# pi3_hat.net
KiCad netlist of a schematic drawn in EAGLE
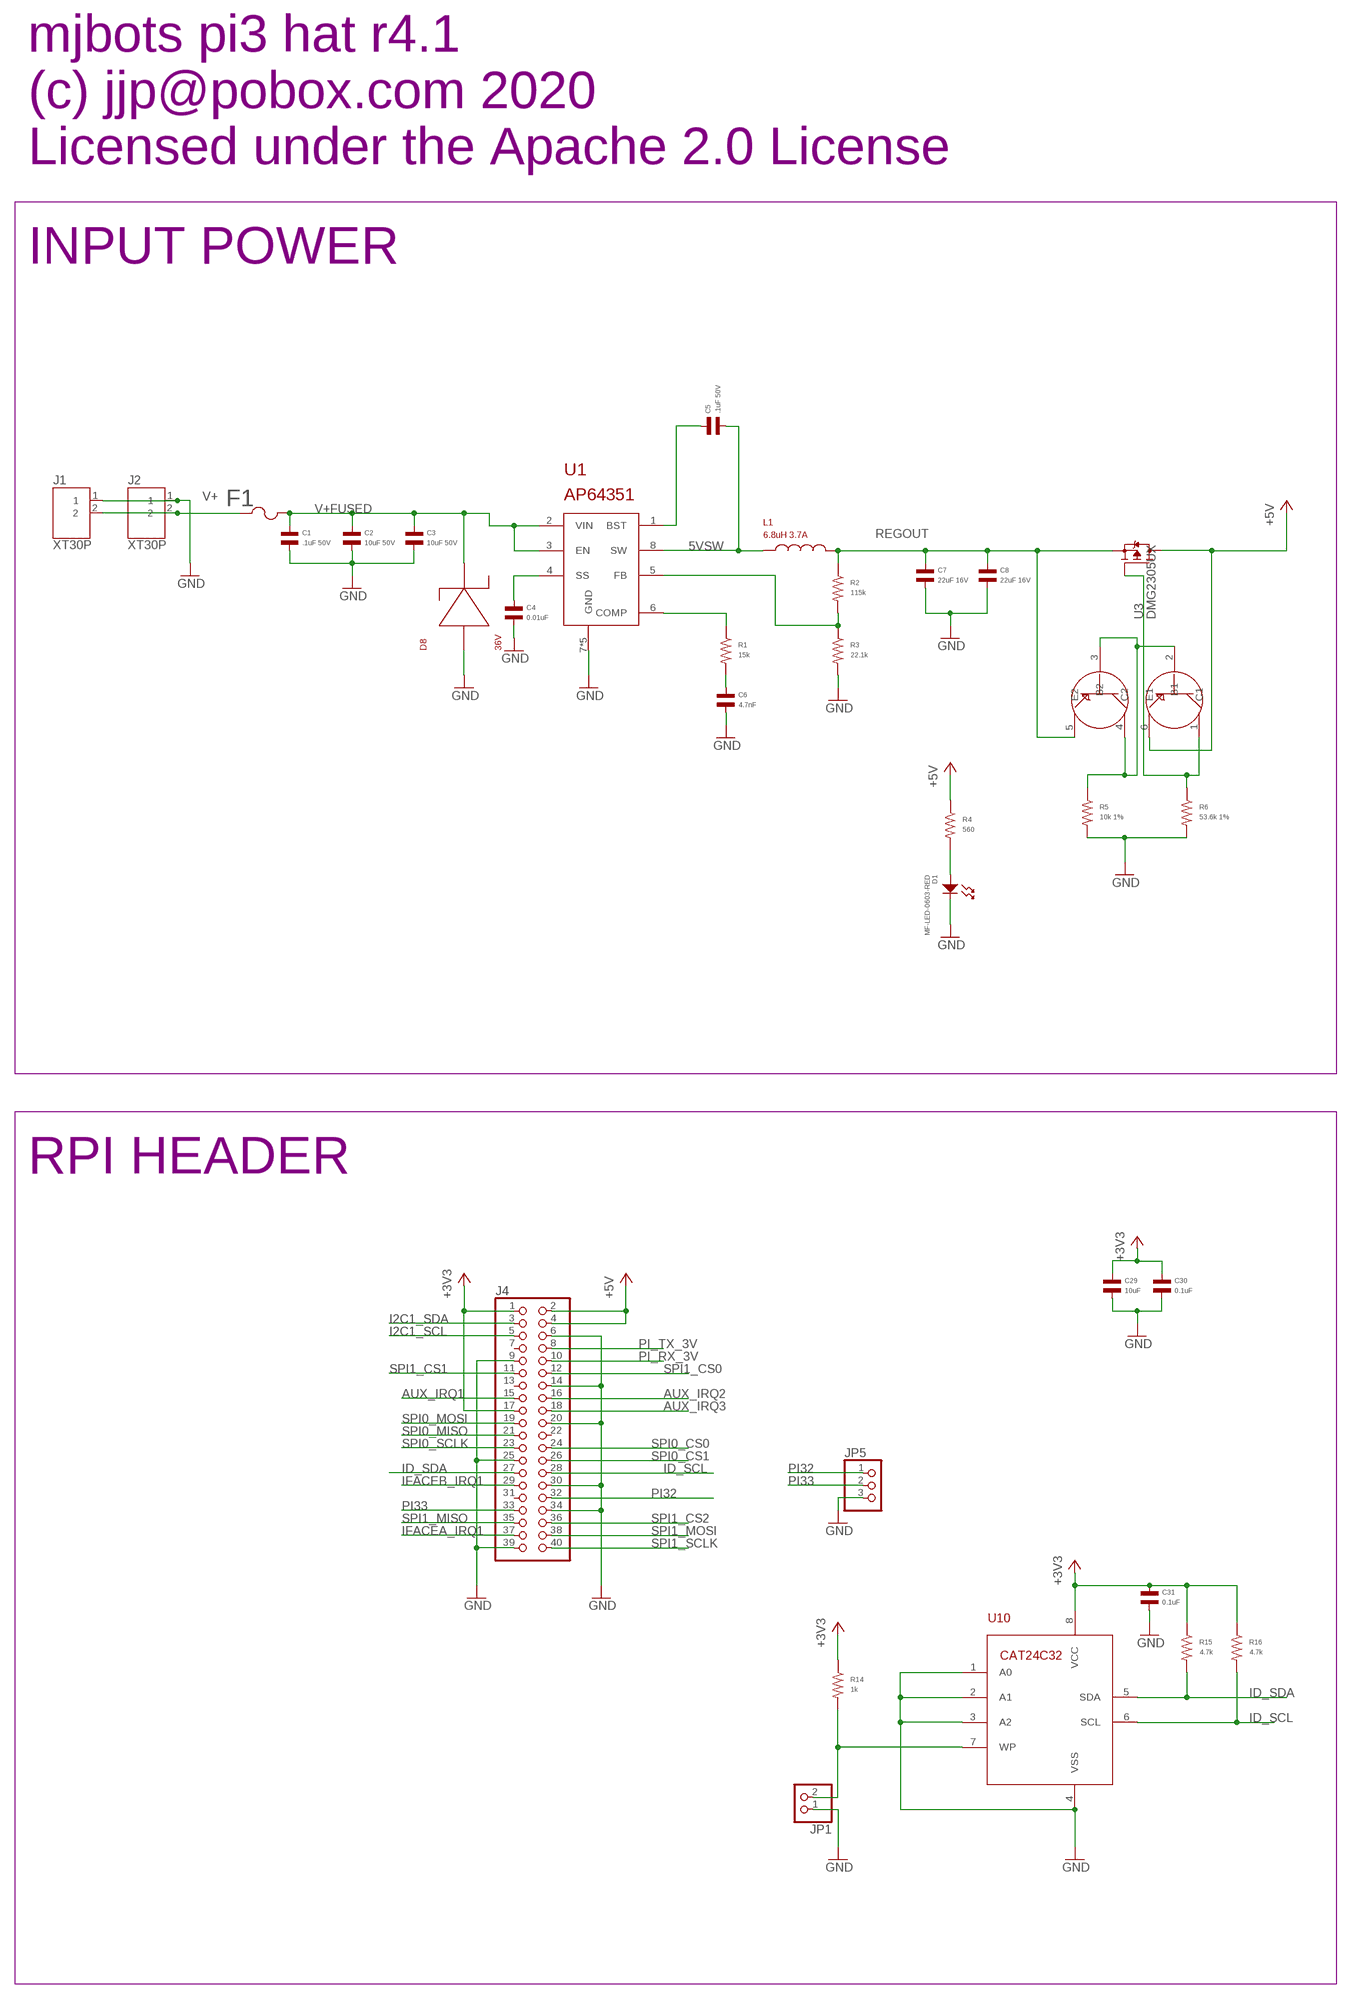
[diagram p0: schematic, sheet 1, part 1 of 3]
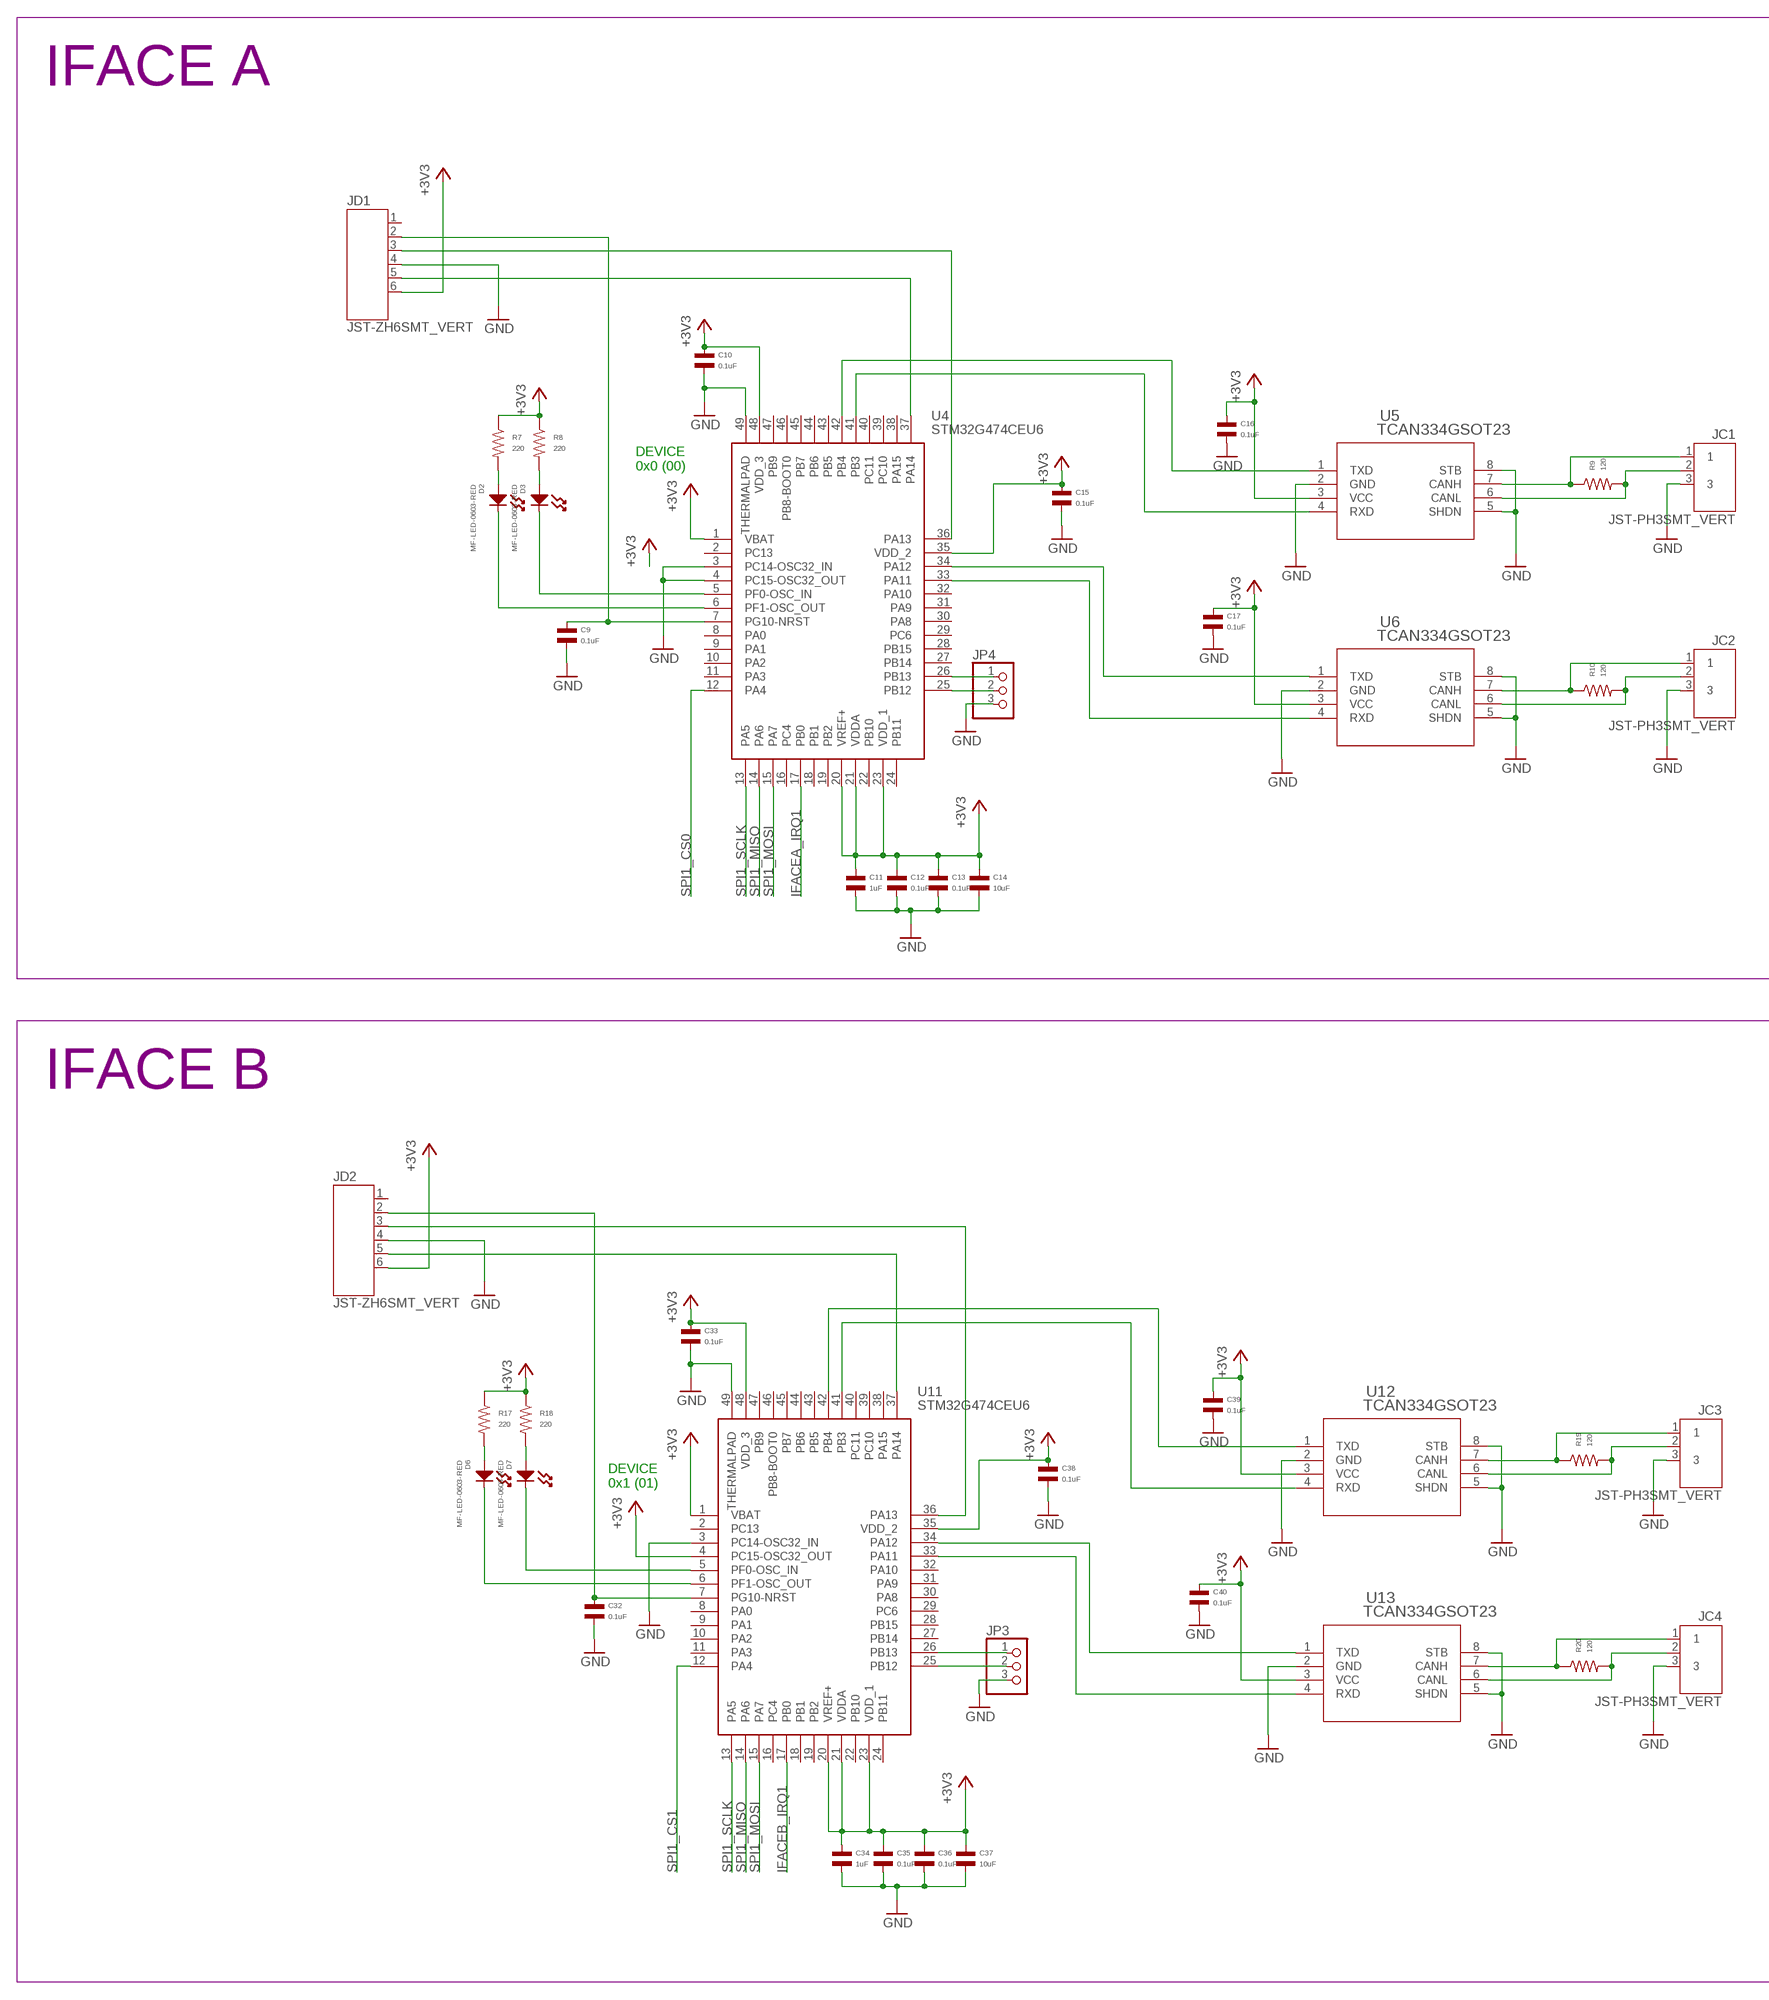
[diagram p1: schematic, sheet 1, part 2 of 3]
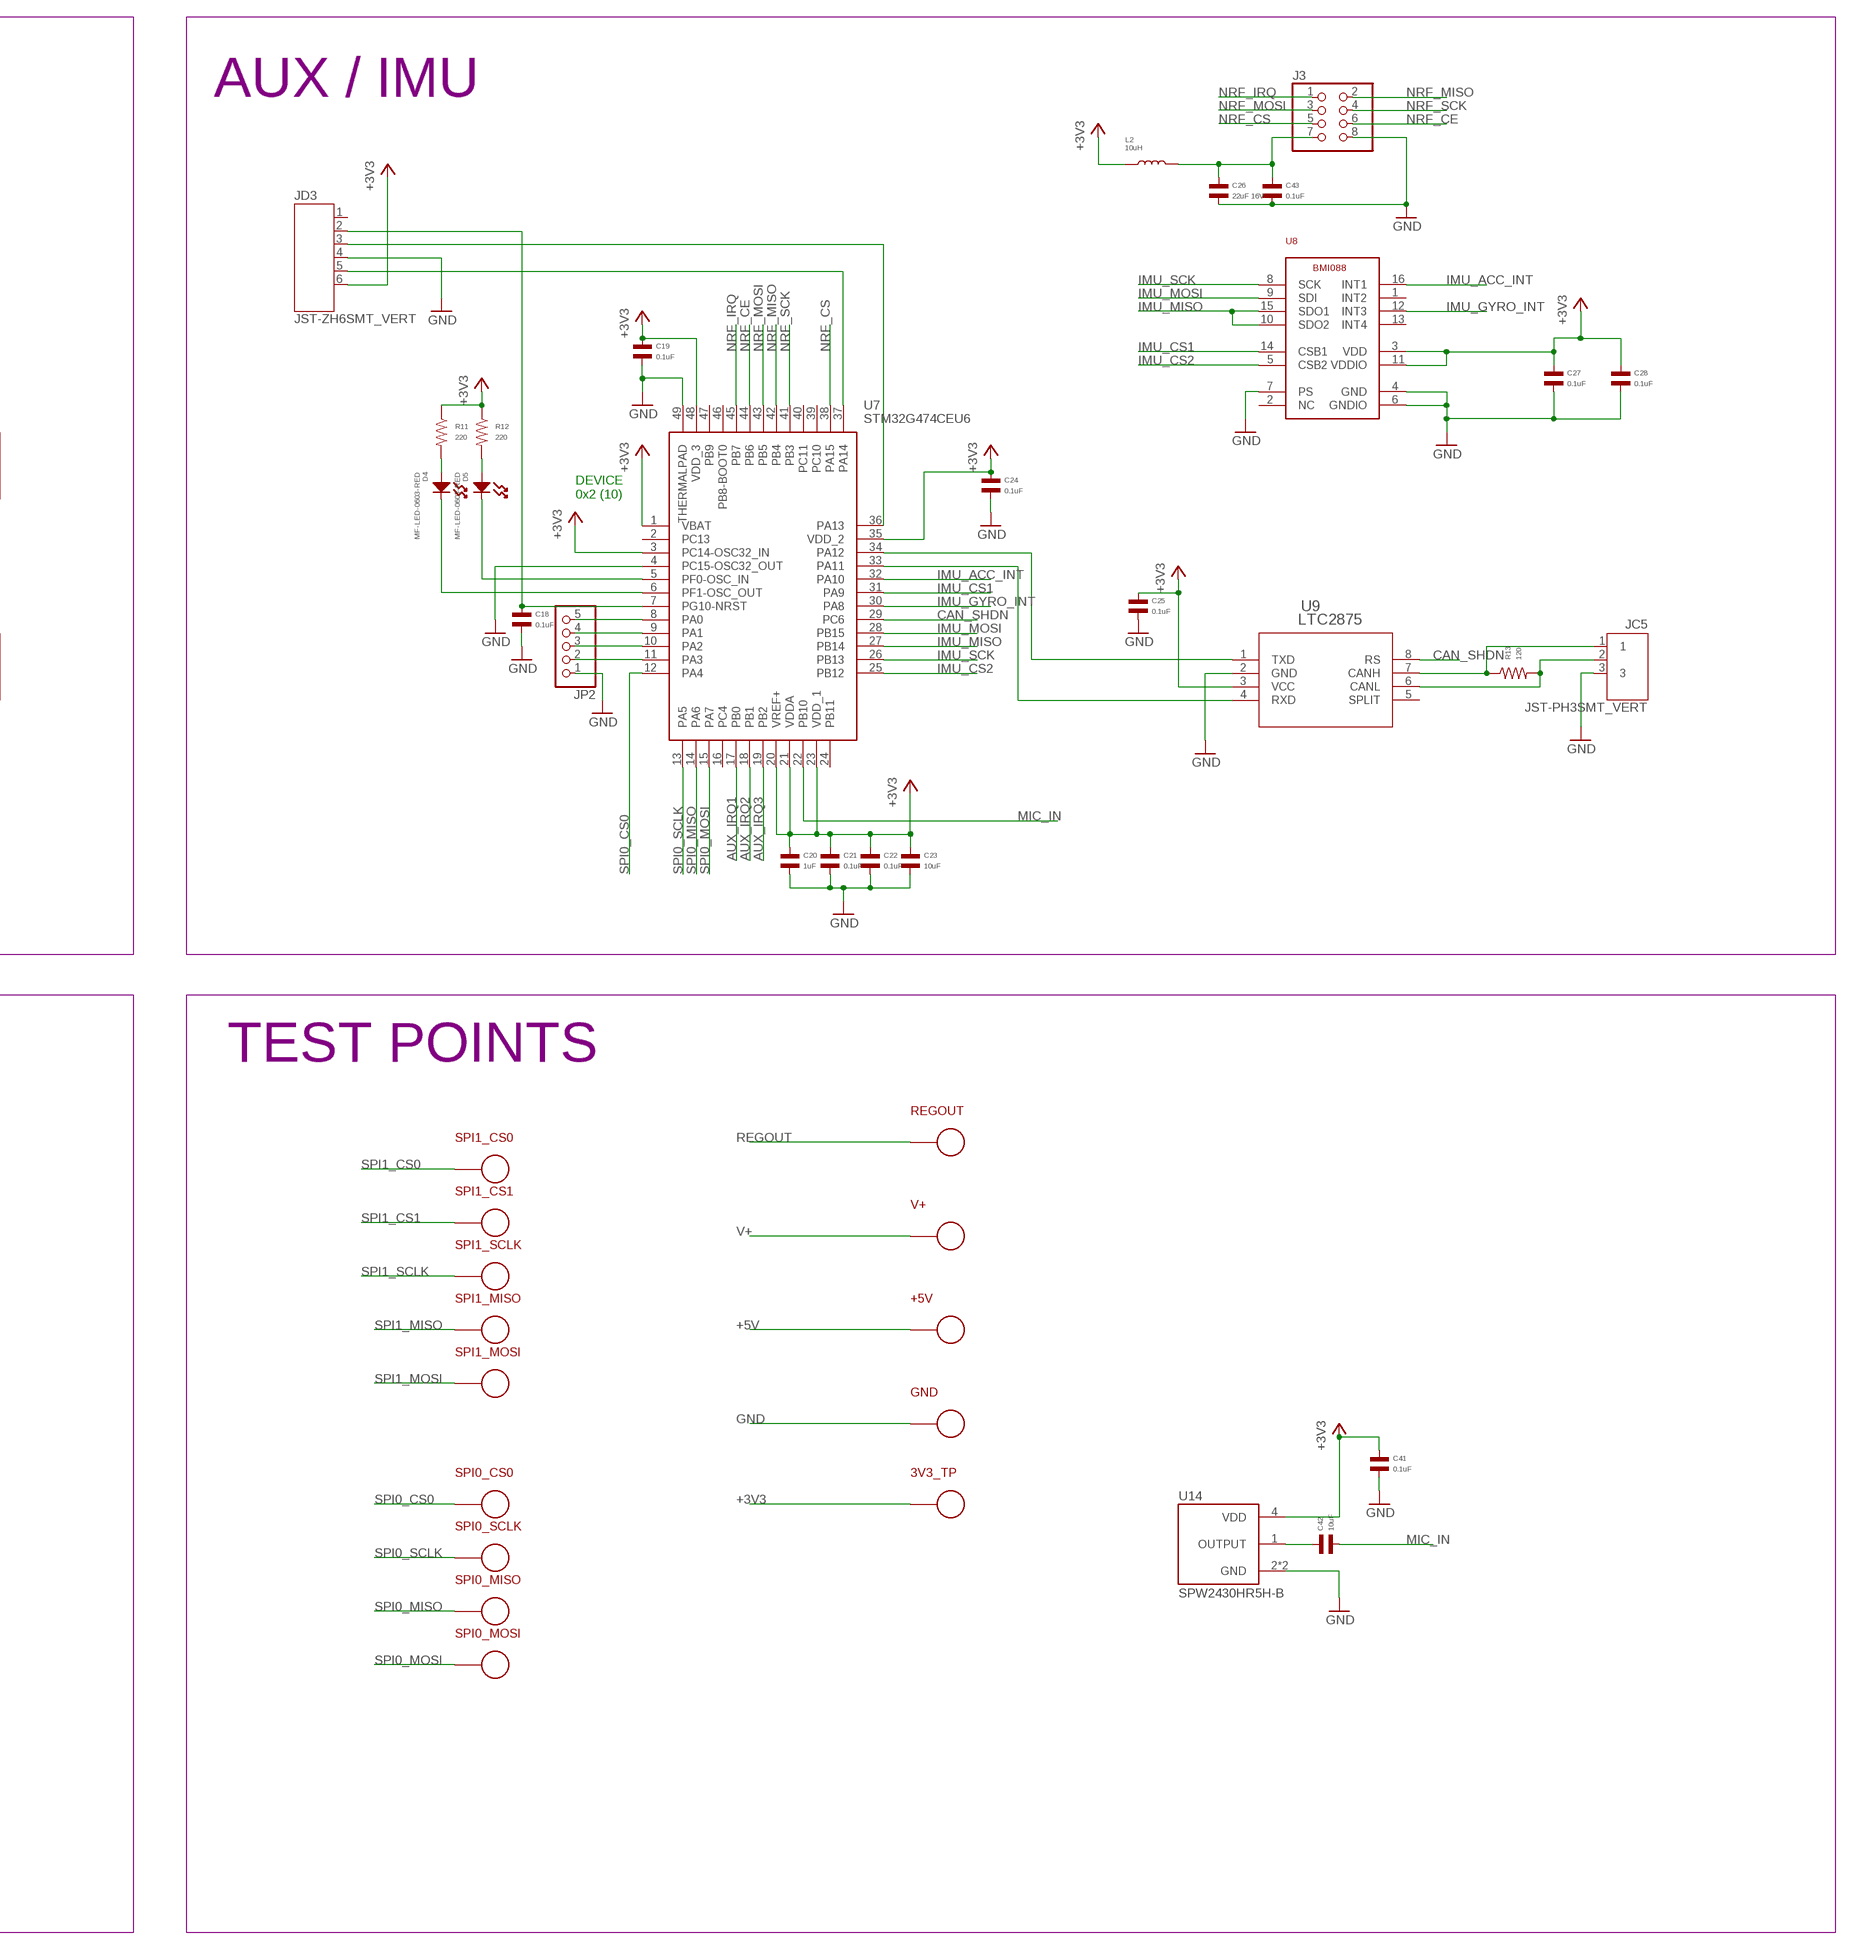
[diagram p2: schematic, sheet 1, part 3 of 3]

(export (version "E")
  (design (tool "Eeschema 10.0.6"))
  (components
    (comp (ref "+5V")
      (value "PAD24AWG_PAD")
      (footprint "eagle-import:24AWG_PAD")
      (libsource (lib "eagle-import") (part "PAD24AWG_PAD"))
    )
    (comp (ref "3V3_TP")
      (value "PAD24AWG_PAD")
      (footprint "eagle-import:24AWG_PAD")
      (libsource (lib "eagle-import") (part "PAD24AWG_PAD"))
    )
    (comp (ref "C1")
      (value ".1uF 50V")
      (footprint "eagle-import:C0805")
      (fields (field (name "HOUSEPART") "1") (field (name "MPN") "MF-CAP-0805-0.1uF"))
      (libsource (lib "eagle-import") (part "CAPACITOR_NP_0805"))
    )
    (comp (ref "C2")
      (value "10uF 50V")
      (footprint "eagle-import:C1206")
      (fields (field (name "MF") "TDK") (field (name "MPN") "CGA5L1X7R1H106K160AC"))
      (libsource (lib "eagle-import") (part "CAPACITOR_NP_1206"))
    )
    (comp (ref "C3")
      (value "10uF 50V")
      (footprint "eagle-import:C1206")
      (fields (field (name "MF") "TDK") (field (name "MPN") "CGA5L1X7R1H106K160AC"))
      (libsource (lib "eagle-import") (part "CAPACITOR_NP_1206"))
    )
    (comp (ref "C4")
      (value "0.01uF")
      (footprint "eagle-import:C0603")
      (fields (field (name "MPN") "MF-CAP-0603-0.01uF"))
      (libsource (lib "eagle-import") (part "CAPACITOR_NP_0603"))
    )
    (comp (ref "C5")
      (value ".1uF 50V")
      (footprint "eagle-import:C0805")
      (fields (field (name "HOUSEPART") "1") (field (name "MPN") "MF-CAP-0805-0.1uF"))
      (libsource (lib "eagle-import") (part "CAPACITOR_NP_0805"))
    )
    (comp (ref "C6")
      (value "4.7nF")
      (footprint "eagle-import:C0402")
      (fields (field (name "HOUSEPART") "YES") (field (name "MPN") "MF-CAP-0402-4.7nF"))
      (libsource (lib "eagle-import") (part "CAPACITOR_NP_0402"))
    )
    (comp (ref "C7")
      (value "22uF 16V")
      (footprint "eagle-import:C1210")
      (fields (field (name "MF") "SAMSUNG") (field (name "MPN") "CL32A226KOJNNNE"))
      (libsource (lib "eagle-import") (part "CAPACITOR_NP_1210"))
    )
    (comp (ref "C8")
      (value "22uF 16V")
      (footprint "eagle-import:C1210")
      (fields (field (name "MF") "SAMSUNG") (field (name "MPN") "CL32A226KOJNNNE"))
      (libsource (lib "eagle-import") (part "CAPACITOR_NP_1210"))
    )
    (comp (ref "C9")
      (value "0.1uF")
      (footprint "eagle-import:C0402")
      (fields (field (name "HOUSEPART") "YES") (field (name "MPN") "MF-CAP-0402-0.1uF"))
      (libsource (lib "eagle-import") (part "CAPACITOR_NP_0402"))
    )
    (comp (ref "C10")
      (value "0.1uF")
      (footprint "eagle-import:C0402")
      (fields (field (name "HOUSEPART") "YES") (field (name "MPN") "MF-CAP-0402-0.1uF"))
      (libsource (lib "eagle-import") (part "CAPACITOR_NP_0402"))
    )
    (comp (ref "C11")
      (value "1uF")
      (footprint "eagle-import:C0402")
      (fields (field (name "HOUSEPART") "YES") (field (name "MPN") "MF-CAP-0402-1uF"))
      (libsource (lib "eagle-import") (part "CAPACITOR_NP_0402"))
    )
    (comp (ref "C12")
      (value "0.1uF")
      (footprint "eagle-import:C0402")
      (fields (field (name "HOUSEPART") "YES") (field (name "MPN") "MF-CAP-0402-0.1uF"))
      (libsource (lib "eagle-import") (part "CAPACITOR_NP_0402"))
    )
    (comp (ref "C13")
      (value "0.1uF")
      (footprint "eagle-import:C0402")
      (fields (field (name "HOUSEPART") "YES") (field (name "MPN") "MF-CAP-0402-0.1uF"))
      (libsource (lib "eagle-import") (part "CAPACITOR_NP_0402"))
    )
    (comp (ref "C14")
      (value "10uF")
      (footprint "eagle-import:C1206")
      (fields (field (name "HOUSEPART") "YES") (field (name "MPN") "MF-CAP-1206-10uF"))
      (libsource (lib "eagle-import") (part "CAPACITOR_NP_1206"))
    )
    (comp (ref "C15")
      (value "0.1uF")
      (footprint "eagle-import:C0402")
      (fields (field (name "HOUSEPART") "YES") (field (name "MPN") "MF-CAP-0402-0.1uF"))
      (libsource (lib "eagle-import") (part "CAPACITOR_NP_0402"))
    )
    (comp (ref "C16")
      (value "0.1uF")
      (footprint "eagle-import:C0402")
      (fields (field (name "HOUSEPART") "YES") (field (name "MPN") "MF-CAP-0402-0.1uF"))
      (libsource (lib "eagle-import") (part "CAPACITOR_NP_0402"))
    )
    (comp (ref "C17")
      (value "0.1uF")
      (footprint "eagle-import:C0402")
      (fields (field (name "HOUSEPART") "YES") (field (name "MPN") "MF-CAP-0402-0.1uF"))
      (libsource (lib "eagle-import") (part "CAPACITOR_NP_0402"))
    )
    (comp (ref "C18")
      (value "0.1uF")
      (footprint "eagle-import:C0402")
      (fields (field (name "HOUSEPART") "YES") (field (name "MPN") "MF-CAP-0402-0.1uF"))
      (libsource (lib "eagle-import") (part "CAPACITOR_NP_0402"))
    )
    (comp (ref "C19")
      (value "0.1uF")
      (footprint "eagle-import:C0402")
      (fields (field (name "HOUSEPART") "YES") (field (name "MPN") "MF-CAP-0402-0.1uF"))
      (libsource (lib "eagle-import") (part "CAPACITOR_NP_0402"))
    )
    (comp (ref "C20")
      (value "1uF")
      (footprint "eagle-import:C0402")
      (fields (field (name "HOUSEPART") "YES") (field (name "MPN") "MF-CAP-0402-1uF"))
      (libsource (lib "eagle-import") (part "CAPACITOR_NP_0402"))
    )
    (comp (ref "C21")
      (value "0.1uF")
      (footprint "eagle-import:C0402")
      (fields (field (name "HOUSEPART") "YES") (field (name "MPN") "MF-CAP-0402-0.1uF"))
      (libsource (lib "eagle-import") (part "CAPACITOR_NP_0402"))
    )
    (comp (ref "C22")
      (value "0.1uF")
      (footprint "eagle-import:C0402")
      (fields (field (name "HOUSEPART") "YES") (field (name "MPN") "MF-CAP-0402-0.1uF"))
      (libsource (lib "eagle-import") (part "CAPACITOR_NP_0402"))
    )
    (comp (ref "C23")
      (value "10uF")
      (footprint "eagle-import:C1206")
      (fields (field (name "HOUSEPART") "YES") (field (name "MPN") "MF-CAP-1206-10uF"))
      (libsource (lib "eagle-import") (part "CAPACITOR_NP_1206"))
    )
    (comp (ref "C24")
      (value "0.1uF")
      (footprint "eagle-import:C0402")
      (fields (field (name "HOUSEPART") "YES") (field (name "MPN") "MF-CAP-0402-0.1uF"))
      (libsource (lib "eagle-import") (part "CAPACITOR_NP_0402"))
    )
    (comp (ref "C25")
      (value "0.1uF")
      (footprint "eagle-import:C0402")
      (fields (field (name "HOUSEPART") "YES") (field (name "MPN") "MF-CAP-0402-0.1uF"))
      (libsource (lib "eagle-import") (part "CAPACITOR_NP_0402"))
    )
    (comp (ref "C26")
      (value "22uF 16V")
      (footprint "eagle-import:C1210")
      (fields (field (name "MF") "SAMSUNG") (field (name "MPN") "CL32A226KOJNNNE"))
      (libsource (lib "eagle-import") (part "CAPACITOR_NP_1210"))
    )
    (comp (ref "C27")
      (value "0.1uF")
      (footprint "eagle-import:C0402")
      (fields (field (name "HOUSEPART") "YES") (field (name "MPN") "MF-CAP-0402-0.1uF"))
      (libsource (lib "eagle-import") (part "CAPACITOR_NP_0402"))
    )
    (comp (ref "C28")
      (value "0.1uF")
      (footprint "eagle-import:C0402")
      (fields (field (name "HOUSEPART") "YES") (field (name "MPN") "MF-CAP-0402-0.1uF"))
      (libsource (lib "eagle-import") (part "CAPACITOR_NP_0402"))
    )
    (comp (ref "C29")
      (value "10uF")
      (footprint "eagle-import:C1206")
      (fields (field (name "HOUSEPART") "YES") (field (name "MPN") "MF-CAP-1206-10uF"))
      (libsource (lib "eagle-import") (part "CAPACITOR_NP_1206"))
    )
    (comp (ref "C30")
      (value "0.1uF")
      (footprint "eagle-import:C0402")
      (fields (field (name "HOUSEPART") "YES") (field (name "MPN") "MF-CAP-0402-0.1uF"))
      (libsource (lib "eagle-import") (part "CAPACITOR_NP_0402"))
    )
    (comp (ref "C31")
      (value "0.1uF")
      (footprint "eagle-import:C0402")
      (fields (field (name "HOUSEPART") "YES") (field (name "MPN") "MF-CAP-0402-0.1uF"))
      (libsource (lib "eagle-import") (part "CAPACITOR_NP_0402"))
    )
    (comp (ref "C32")
      (value "0.1uF")
      (footprint "eagle-import:C0402")
      (fields (field (name "HOUSEPART") "YES") (field (name "MPN") "MF-CAP-0402-0.1uF"))
      (libsource (lib "eagle-import") (part "CAPACITOR_NP_0402"))
    )
    (comp (ref "C33")
      (value "0.1uF")
      (footprint "eagle-import:C0402")
      (fields (field (name "HOUSEPART") "YES") (field (name "MPN") "MF-CAP-0402-0.1uF"))
      (libsource (lib "eagle-import") (part "CAPACITOR_NP_0402"))
    )
    (comp (ref "C34")
      (value "1uF")
      (footprint "eagle-import:C0402")
      (fields (field (name "HOUSEPART") "YES") (field (name "MPN") "MF-CAP-0402-1uF"))
      (libsource (lib "eagle-import") (part "CAPACITOR_NP_0402"))
    )
    (comp (ref "C35")
      (value "0.1uF")
      (footprint "eagle-import:C0402")
      (fields (field (name "HOUSEPART") "YES") (field (name "MPN") "MF-CAP-0402-0.1uF"))
      (libsource (lib "eagle-import") (part "CAPACITOR_NP_0402"))
    )
    (comp (ref "C36")
      (value "0.1uF")
      (footprint "eagle-import:C0402")
      (fields (field (name "HOUSEPART") "YES") (field (name "MPN") "MF-CAP-0402-0.1uF"))
      (libsource (lib "eagle-import") (part "CAPACITOR_NP_0402"))
    )
    (comp (ref "C37")
      (value "10uF")
      (footprint "eagle-import:C1206")
      (fields (field (name "HOUSEPART") "YES") (field (name "MPN") "MF-CAP-1206-10uF"))
      (libsource (lib "eagle-import") (part "CAPACITOR_NP_1206"))
    )
    (comp (ref "C38")
      (value "0.1uF")
      (footprint "eagle-import:C0402")
      (fields (field (name "HOUSEPART") "YES") (field (name "MPN") "MF-CAP-0402-0.1uF"))
      (libsource (lib "eagle-import") (part "CAPACITOR_NP_0402"))
    )
    (comp (ref "C39")
      (value "0.1uF")
      (footprint "eagle-import:C0402")
      (fields (field (name "HOUSEPART") "YES") (field (name "MPN") "MF-CAP-0402-0.1uF"))
      (libsource (lib "eagle-import") (part "CAPACITOR_NP_0402"))
    )
    (comp (ref "C40")
      (value "0.1uF")
      (footprint "eagle-import:C0402")
      (fields (field (name "HOUSEPART") "YES") (field (name "MPN") "MF-CAP-0402-0.1uF"))
      (libsource (lib "eagle-import") (part "CAPACITOR_NP_0402"))
    )
    (comp (ref "C41")
      (value "0.1uF")
      (footprint "eagle-import:C0402")
      (fields (field (name "HOUSEPART") "YES") (field (name "MPN") "MF-CAP-0402-0.1uF"))
      (libsource (lib "eagle-import") (part "CAPACITOR_NP_0402"))
    )
    (comp (ref "C42")
      (value "10uF")
      (footprint "eagle-import:C1206")
      (fields (field (name "HOUSEPART") "YES") (field (name "MPN") "MF-CAP-1206-10uF"))
      (libsource (lib "eagle-import") (part "CAPACITOR_NP_1206"))
    )
    (comp (ref "C43")
      (value "0.1uF")
      (footprint "eagle-import:C0402")
      (fields (field (name "HOUSEPART") "YES") (field (name "MPN") "MF-CAP-0402-0.1uF"))
      (libsource (lib "eagle-import") (part "CAPACITOR_NP_0402"))
    )
    (comp (ref "D1")
      (value "MF-LED-0603-RED")
      (footprint "eagle-import:LED0603")
      (fields (field (name "HOUSEPART") "YES"))
      (libsource (lib "eagle-import") (part "LED_SINGLE-0603-RED"))
    )
    (comp (ref "D2")
      (value "MF-LED-0603-RED")
      (footprint "eagle-import:LED0603")
      (fields (field (name "HOUSEPART") "YES"))
      (libsource (lib "eagle-import") (part "LED_SINGLE-0603-RED"))
    )
    (comp (ref "D3")
      (value "MF-LED-0603-RED")
      (footprint "eagle-import:LED0603")
      (fields (field (name "HOUSEPART") "YES") (field (name "MPN") "MF-LED-0603-GREEN"))
      (libsource (lib "eagle-import") (part "LED_SINGLE-0603-RED"))
    )
    (comp (ref "D4")
      (value "MF-LED-0603-RED")
      (footprint "eagle-import:LED0603")
      (fields (field (name "HOUSEPART") "YES"))
      (libsource (lib "eagle-import") (part "LED_SINGLE-0603-RED"))
    )
    (comp (ref "D5")
      (value "MF-LED-0603-RED")
      (footprint "eagle-import:LED0603")
      (fields (field (name "HOUSEPART") "YES") (field (name "MPN") "MF-LED-0603-GREEN"))
      (libsource (lib "eagle-import") (part "LED_SINGLE-0603-RED"))
    )
    (comp (ref "D6")
      (value "MF-LED-0603-RED")
      (footprint "eagle-import:LED0603")
      (fields (field (name "HOUSEPART") "YES"))
      (libsource (lib "eagle-import") (part "LED_SINGLE-0603-RED"))
    )
    (comp (ref "D7")
      (value "MF-LED-0603-RED")
      (footprint "eagle-import:LED0603")
      (fields (field (name "HOUSEPART") "YES") (field (name "MPN") "MF-LED-0603-GREEN"))
      (libsource (lib "eagle-import") (part "LED_SINGLE-0603-RED"))
    )
    (comp (ref "D8")
      (value "36V")
      (footprint "eagle-import:SMF")
      (fields (field (name "MF") "Vishay") (field (name "MPN") "SMF36A-E3-08"))
      (libsource (lib "eagle-import") (part "SMF"))
    )
    (comp (ref "F1")
      (value "MFU0603FF04000P100")
      (footprint "eagle-import:FUS_VISHAY_MFU0603")
      (fields (field (name "MF") "VISHAY"))
      (libsource (lib "eagle-import") (part "MFU0603FF04000P100"))
    )
    (comp (ref "GND")
      (value "PAD24AWG_PAD")
      (footprint "eagle-import:24AWG_PAD")
      (libsource (lib "eagle-import") (part "PAD24AWG_PAD"))
    )
    (comp (ref "J1")
      (value "XT30P")
      (footprint "eagle-import:XT30P")
      (libsource (lib "eagle-import") (part "XT30P"))
    )
    (comp (ref "J2")
      (value "XT30P")
      (footprint "eagle-import:XT30P")
      (libsource (lib "eagle-import") (part "XT30P"))
    )
    (comp (ref "J3")
      (value "PINHD-2X4")
      (footprint "eagle-import:2X04")
      (libsource (lib "eagle-import") (part "PINHD-2X4"))
    )
    (comp (ref "J4")
      (value "PI3_HEADER2X20-FLIP")
      (footprint "eagle-import:2X20FLIP")
      (fields (field (name "MF") "Sullins") (field (name "MPN") "PPPC202LFBN-RC"))
      (libsource (lib "eagle-import") (part "PI3_HEADER2X20-FLIP"))
    )
    (comp (ref "JC1")
      (value "JST-PH3SMT_VERT")
      (footprint "eagle-import:JST_B3B_PH-SM4-TB(LF)(SN)")
      (fields (field (name "MF") "JST") (field (name "MPN") "B3B-PH-SM4-TB(LF)(SN)"))
      (libsource (lib "eagle-import") (part "JST-PH3SMT_VERT"))
    )
    (comp (ref "JC2")
      (value "JST-PH3SMT_VERT")
      (footprint "eagle-import:JST_B3B_PH-SM4-TB(LF)(SN)")
      (fields (field (name "MF") "JST") (field (name "MPN") "B3B-PH-SM4-TB(LF)(SN)"))
      (libsource (lib "eagle-import") (part "JST-PH3SMT_VERT"))
    )
    (comp (ref "JC3")
      (value "JST-PH3SMT_VERT")
      (footprint "eagle-import:JST_B3B_PH-SM4-TB(LF)(SN)")
      (fields (field (name "MF") "JST") (field (name "MPN") "B3B-PH-SM4-TB(LF)(SN)"))
      (libsource (lib "eagle-import") (part "JST-PH3SMT_VERT"))
    )
    (comp (ref "JC4")
      (value "JST-PH3SMT_VERT")
      (footprint "eagle-import:JST_B3B_PH-SM4-TB(LF)(SN)")
      (fields (field (name "MF") "JST") (field (name "MPN") "B3B-PH-SM4-TB(LF)(SN)"))
      (libsource (lib "eagle-import") (part "JST-PH3SMT_VERT"))
    )
    (comp (ref "JC5")
      (value "JST-PH3SMT_VERT")
      (footprint "eagle-import:JST_B3B_PH-SM4-TB(LF)(SN)")
      (fields (field (name "MF") "JST") (field (name "MPN") "B3B-PH-SM4-TB(LF)(SN)"))
      (libsource (lib "eagle-import") (part "JST-PH3SMT_VERT"))
    )
    (comp (ref "JD1")
      (value "JST-ZH6SMT_VERT")
      (footprint "eagle-import:JST_B6B-ZR-SM4-TF(LF)(SN)")
      (fields (field (name "MF") "JST") (field (name "MPN") "B6B-ZR-SM4-TF(LF)(SN)"))
      (libsource (lib "eagle-import") (part "JST-ZH6SMT_VERT"))
    )
    (comp (ref "JD2")
      (value "JST-ZH6SMT_VERT")
      (footprint "eagle-import:JST_B6B-ZR-SM4-TF(LF)(SN)")
      (fields (field (name "MF") "JST") (field (name "MPN") "B6B-ZR-SM4-TF(LF)(SN)"))
      (libsource (lib "eagle-import") (part "JST-ZH6SMT_VERT"))
    )
    (comp (ref "JD3")
      (value "JST-ZH6SMT_VERT")
      (footprint "eagle-import:JST_B6B-ZR-SM4-TF(LF)(SN)")
      (fields (field (name "MF") "JST") (field (name "MPN") "B6B-ZR-SM4-TF(LF)(SN)"))
      (libsource (lib "eagle-import") (part "JST-ZH6SMT_VERT"))
    )
    (comp (ref "JP1")
      (value "PINHD-1X2")
      (footprint "eagle-import:1X02")
      (fields (field (name "HOUSEPART") "YES") (field (name "MPN") "MF-CON-2.54mm-01x02"))
      (libsource (lib "eagle-import") (part "PINHD-1X2"))
    )
    (comp (ref "JP2")
      (value "PINHD-1X5")
      (footprint "eagle-import:1X05")
      (fields (field (name "MF") "MacroFab") (field (name "MPN") "MF-CON-2.54mm-01x05"))
      (libsource (lib "eagle-import") (part "PINHD-1X5"))
    )
    (comp (ref "JP3")
      (value "PINHD-1X3")
      (footprint "eagle-import:1X03")
      (fields (field (name "MF") "MacroFab") (field (name "MPN") "MF-CON-2.54mm-01x03"))
      (libsource (lib "eagle-import") (part "PINHD-1X3"))
    )
    (comp (ref "JP4")
      (value "PINHD-1X3")
      (footprint "eagle-import:1X03")
      (fields (field (name "MF") "MacroFab") (field (name "MPN") "MF-CON-2.54mm-01x03"))
      (libsource (lib "eagle-import") (part "PINHD-1X3"))
    )
    (comp (ref "JP5")
      (value "PINHD-1X3")
      (footprint "eagle-import:1X03")
      (fields (field (name "MF") "MacroFab") (field (name "MPN") "MF-CON-2.54mm-01x03"))
      (libsource (lib "eagle-import") (part "PINHD-1X3"))
    )
    (comp (ref "L1")
      (value "6.8uH 3.7A")
      (footprint "eagle-import:TAIYO_8040")
      (fields
        (field (name "HOUSEPART") "0")
        (field (name "MF") "TAIYO YUDEN")
        (field (name "MPN") "NR8040T6R8N")
      )
      (libsource (lib "eagle-import") (part "INDUCTORTAIYO_8040"))
    )
    (comp (ref "L2")
      (value "10uH")
      (footprint "eagle-import:L1210")
      (fields (field (name "MPN") "MF-IND-1210-10uH"))
      (libsource (lib "eagle-import") (part "INDUCTOR_1210"))
    )
    (comp (ref "R1")
      (value "15k")
      (footprint "eagle-import:R0402")
      (fields (field (name "HOUSEPART") "YES") (field (name "MPN") "MF-RES-0402-15K"))
      (libsource (lib "eagle-import") (part "RESISTOR_0402"))
    )
    (comp (ref "R2")
      (value "115k")
      (footprint "eagle-import:R0402")
      (fields (field (name "MF") "YAGEO") (field (name "MPN") "RC0402FR-07115KL"))
      (libsource (lib "eagle-import") (part "RESISTOR_0402"))
    )
    (comp (ref "R3")
      (value "22.1k")
      (footprint "eagle-import:R0402")
      (fields (field (name "MF") "YAGEO") (field (name "MPN") "RC0402FR-0722K1L"))
      (libsource (lib "eagle-import") (part "RESISTOR_0402"))
    )
    (comp (ref "R4")
      (value "560")
      (footprint "eagle-import:R0402")
      (fields (field (name "HOUSEPART") "YES") (field (name "MPN") "MF-RES-0402-560"))
      (libsource (lib "eagle-import") (part "RESISTOR_0402"))
    )
    (comp (ref "R5")
      (value "10k 1%")
      (footprint "eagle-import:R0603")
      (fields (field (name "MF") "YAGEO") (field (name "MPN") "RC0603FR-0710KL"))
      (libsource (lib "eagle-import") (part "RESISTOR_0603"))
    )
    (comp (ref "R6")
      (value "53.6k 1%")
      (footprint "eagle-import:R0603")
      (fields (field (name "MF") "YAGEO") (field (name "MPN") "RC0603FR-0753K6L"))
      (libsource (lib "eagle-import") (part "RESISTOR_0603"))
    )
    (comp (ref "R7")
      (value "220")
      (footprint "eagle-import:R0402")
      (fields (field (name "HOUSEPART") "YES") (field (name "MPN") "MF-RES-0402-220"))
      (libsource (lib "eagle-import") (part "RESISTOR_0402"))
    )
    (comp (ref "R8")
      (value "220")
      (footprint "eagle-import:R0402")
      (fields (field (name "HOUSEPART") "YES") (field (name "MPN") "MF-RES-0402-220"))
      (libsource (lib "eagle-import") (part "RESISTOR_0402"))
    )
    (comp (ref "R9")
      (value "120")
      (footprint "eagle-import:R0402")
      (fields (field (name "HOUSEPART") "YES") (field (name "MPN") "MF-RES-0402-100"))
      (libsource (lib "eagle-import") (part "RESISTOR_0402"))
    )
    (comp (ref "R10")
      (value "120")
      (footprint "eagle-import:R0402")
      (fields (field (name "HOUSEPART") "YES") (field (name "MPN") "MF-RES-0402-100"))
      (libsource (lib "eagle-import") (part "RESISTOR_0402"))
    )
    (comp (ref "R11")
      (value "220")
      (footprint "eagle-import:R0402")
      (fields (field (name "HOUSEPART") "YES") (field (name "MPN") "MF-RES-0402-220"))
      (libsource (lib "eagle-import") (part "RESISTOR_0402"))
    )
    (comp (ref "R12")
      (value "220")
      (footprint "eagle-import:R0402")
      (fields (field (name "HOUSEPART") "YES") (field (name "MPN") "MF-RES-0402-220"))
      (libsource (lib "eagle-import") (part "RESISTOR_0402"))
    )
    (comp (ref "R13")
      (value "120")
      (footprint "eagle-import:R0402")
      (fields (field (name "HOUSEPART") "YES") (field (name "MPN") "MF-RES-0402-100"))
      (libsource (lib "eagle-import") (part "RESISTOR_0402"))
    )
    (comp (ref "R14")
      (value "1k")
      (footprint "eagle-import:R0402")
      (fields (field (name "HOUSEPART") "YES") (field (name "MPN") "MF-RES-0402-1K"))
      (libsource (lib "eagle-import") (part "RESISTOR_0402"))
    )
    (comp (ref "R15")
      (value "4.7k")
      (footprint "eagle-import:R0402")
      (fields (field (name "HOUSEPART") "YES") (field (name "MPN") "MF-RES-0402-4.7K"))
      (libsource (lib "eagle-import") (part "RESISTOR_0402"))
    )
    (comp (ref "R16")
      (value "4.7k")
      (footprint "eagle-import:R0402")
      (fields (field (name "HOUSEPART") "YES") (field (name "MPN") "MF-RES-0402-4.7K"))
      (libsource (lib "eagle-import") (part "RESISTOR_0402"))
    )
    (comp (ref "R17")
      (value "220")
      (footprint "eagle-import:R0402")
      (fields (field (name "HOUSEPART") "YES") (field (name "MPN") "MF-RES-0402-220"))
      (libsource (lib "eagle-import") (part "RESISTOR_0402"))
    )
    (comp (ref "R18")
      (value "220")
      (footprint "eagle-import:R0402")
      (fields (field (name "HOUSEPART") "YES") (field (name "MPN") "MF-RES-0402-220"))
      (libsource (lib "eagle-import") (part "RESISTOR_0402"))
    )
    (comp (ref "R19")
      (value "120")
      (footprint "eagle-import:R0402")
      (fields (field (name "HOUSEPART") "YES") (field (name "MPN") "MF-RES-0402-100"))
      (libsource (lib "eagle-import") (part "RESISTOR_0402"))
    )
    (comp (ref "R20")
      (value "120")
      (footprint "eagle-import:R0402")
      (fields (field (name "HOUSEPART") "YES") (field (name "MPN") "MF-RES-0402-100"))
      (libsource (lib "eagle-import") (part "RESISTOR_0402"))
    )
    (comp (ref "REGOUT")
      (value "PAD24AWG_PAD")
      (footprint "eagle-import:24AWG_PAD")
      (libsource (lib "eagle-import") (part "PAD24AWG_PAD"))
    )
    (comp (ref "SPI0_CS0")
      (value "PAD24AWG_PAD")
      (footprint "eagle-import:24AWG_PAD")
      (libsource (lib "eagle-import") (part "PAD24AWG_PAD"))
    )
    (comp (ref "SPI0_MISO")
      (value "PAD24AWG_PAD")
      (footprint "eagle-import:24AWG_PAD")
      (libsource (lib "eagle-import") (part "PAD24AWG_PAD"))
    )
    (comp (ref "SPI0_MOSI")
      (value "PAD24AWG_PAD")
      (footprint "eagle-import:24AWG_PAD")
      (libsource (lib "eagle-import") (part "PAD24AWG_PAD"))
    )
    (comp (ref "SPI0_SCLK")
      (value "PAD24AWG_PAD")
      (footprint "eagle-import:24AWG_PAD")
      (libsource (lib "eagle-import") (part "PAD24AWG_PAD"))
    )
    (comp (ref "SPI1_CS0")
      (value "PAD24AWG_PAD")
      (footprint "eagle-import:24AWG_PAD")
      (libsource (lib "eagle-import") (part "PAD24AWG_PAD"))
    )
    (comp (ref "SPI1_CS1")
      (value "PAD24AWG_PAD")
      (footprint "eagle-import:24AWG_PAD")
      (libsource (lib "eagle-import") (part "PAD24AWG_PAD"))
    )
    (comp (ref "SPI1_MISO")
      (value "PAD24AWG_PAD")
      (footprint "eagle-import:24AWG_PAD")
      (libsource (lib "eagle-import") (part "PAD24AWG_PAD"))
    )
    (comp (ref "SPI1_MOSI")
      (value "PAD24AWG_PAD")
      (footprint "eagle-import:24AWG_PAD")
      (libsource (lib "eagle-import") (part "PAD24AWG_PAD"))
    )
    (comp (ref "SPI1_SCLK")
      (value "PAD24AWG_PAD")
      (footprint "eagle-import:24AWG_PAD")
      (libsource (lib "eagle-import") (part "PAD24AWG_PAD"))
    )
    (comp (ref "U1")
      (value "AP64351SO8EP")
      (footprint "eagle-import:SO-8EP")
      (fields
        (field (name "MF") "DIODES INC")
        (field (name "MPN") "AP64350SP-13")
        (field (name "MPN_1") "AP64351SP-13")
      )
      (libsource (lib "eagle-import") (part "AP64351SO8EP"))
    )
    (comp (ref "U2")
      (value "DMMT5401")
      (footprint "eagle-import:SOT26")
      (fields (field (name "MF") "Didoes Incorporated") (field (name "MPN") "DMMT5401-7-F"))
      (libsource (lib "eagle-import") (part "DMMT5401"))
    )
    (comp (ref "U3")
      (value "DMG2305UX")
      (footprint "eagle-import:SOT23")
      (fields (field (name "MF") "Diodes Incorporated") (field (name "MPN") "DMG2305UX-13"))
      (libsource (lib "eagle-import") (part "DMG2305UX"))
    )
    (comp (ref "U4")
      (value "STM32G474CEU6")
      (footprint "eagle-import:QFN50P700X700X60-49N")
      (fields (field (name "MOUSER_PART_NUMBER") "511-STM32G474CEU6") (field (name "MF") "ST"))
      (libsource (lib "eagle-import") (part "STM32G474CEU6"))
    )
    (comp (ref "U5")
      (value "TCAN334GSOT23")
      (footprint "eagle-import:SOT23-8")
      (fields (field (name "MF") "TI") (field (name "MPN") "TCAN334GDCNT"))
      (libsource (lib "eagle-import") (part "TCAN334GSOT23"))
    )
    (comp (ref "U6")
      (value "TCAN334GSOT23")
      (footprint "eagle-import:SOT23-8")
      (fields (field (name "MF") "TI") (field (name "MPN") "TCAN334GDCNT"))
      (libsource (lib "eagle-import") (part "TCAN334GSOT23"))
    )
    (comp (ref "U7")
      (value "STM32G474CEU6")
      (footprint "eagle-import:QFN50P700X700X60-49N")
      (fields (field (name "MOUSER_PART_NUMBER") "511-STM32G474CEU6") (field (name "MF") "ST"))
      (libsource (lib "eagle-import") (part "STM32G474CEU6"))
    )
    (comp (ref "U8")
      (value "BMI088LGA16")
      (footprint "eagle-import:LGA16")
      (fields (field (name "MF") "BOSCH") (field (name "MPN") "BMI088"))
      (libsource (lib "eagle-import") (part "BMI088LGA16"))
    )
    (comp (ref "U9")
      (value "LTC2875")
      (footprint "eagle-import:SOIC8")
      (fields (field (name "MF") "Analog") (field (name "MPN") "LTC2875IS8#PBF"))
      (libsource (lib "eagle-import") (part "LTC2875"))
    )
    (comp (ref "U10")
      (value "CAT24C32SOIC8")
      (footprint "eagle-import:SOIC8")
      (fields (field (name "MF") "ON Semiconductor") (field (name "MPN") "CAT24C32WI-GT3"))
      (libsource (lib "eagle-import") (part "CAT24C32SOIC8"))
    )
    (comp (ref "U11")
      (value "STM32G474CEU6")
      (footprint "eagle-import:QFN50P700X700X60-49N")
      (fields (field (name "MOUSER_PART_NUMBER") "511-STM32G474CEU6") (field (name "MF") "ST"))
      (libsource (lib "eagle-import") (part "STM32G474CEU6"))
    )
    (comp (ref "U12")
      (value "TCAN334GSOT23")
      (footprint "eagle-import:SOT23-8")
      (fields (field (name "MF") "TI") (field (name "MPN") "TCAN334GDCNT"))
      (libsource (lib "eagle-import") (part "TCAN334GSOT23"))
    )
    (comp (ref "U13")
      (value "TCAN334GSOT23")
      (footprint "eagle-import:SOT23-8")
      (fields (field (name "MF") "TI") (field (name "MPN") "TCAN334GDCNT"))
      (libsource (lib "eagle-import") (part "TCAN334GSOT23"))
    )
    (comp (ref "U14")
      (value "SPW2430HR5H-B")
      (footprint "eagle-import:MIC_SPW2430HR5H-B")
      (fields (field (name "DIGI-KEY_PART_NUMBER") "423-1394-1-ND") (field (name "MF") "Knowles"))
      (libsource (lib "eagle-import") (part "SPW2430HR5H-B"))
    )
    (comp (ref "V+")
      (value "PAD24AWG_PAD")
      (footprint "eagle-import:24AWG_PAD")
      (libsource (lib "eagle-import") (part "PAD24AWG_PAD"))
    )
  )
  (nets
    (net (code "1") (name "+3V3") (class "Default")
      (node (ref "3V3_TP") (pin "P$1") (pinfunction "P$1_P$1") (pintype "bidirectional"))
      (node (ref "C10") (pin "P$1") (pinfunction "P$1_P$1") (pintype "passive"))
      (node (ref "C11") (pin "P$1") (pinfunction "P$1_P$1") (pintype "passive"))
      (node (ref "C12") (pin "P$1") (pinfunction "P$1_P$1") (pintype "passive"))
      (node (ref "C13") (pin "P$1") (pinfunction "P$1_P$1") (pintype "passive"))
      (node (ref "C14") (pin "P$1") (pinfunction "P$1_P$1") (pintype "passive"))
      (node (ref "C15") (pin "P$1") (pinfunction "P$1_P$1") (pintype "passive"))
      (node (ref "C16") (pin "P$1") (pinfunction "P$1_P$1") (pintype "passive"))
      (node (ref "C17") (pin "P$1") (pinfunction "P$1_P$1") (pintype "passive"))
      (node (ref "C19") (pin "P$1") (pinfunction "P$1_P$1") (pintype "passive"))
      (node (ref "C20") (pin "P$1") (pinfunction "P$1_P$1") (pintype "passive"))
      (node (ref "C21") (pin "P$1") (pinfunction "P$1_P$1") (pintype "passive"))
      (node (ref "C22") (pin "P$1") (pinfunction "P$1_P$1") (pintype "passive"))
      (node (ref "C23") (pin "P$1") (pinfunction "P$1_P$1") (pintype "passive"))
      (node (ref "C24") (pin "P$1") (pinfunction "P$1_P$1") (pintype "passive"))
      (node (ref "C25") (pin "P$1") (pinfunction "P$1_P$1") (pintype "passive"))
      (node (ref "C27") (pin "P$1") (pinfunction "P$1_P$1") (pintype "passive"))
      (node (ref "C28") (pin "P$1") (pinfunction "P$1_P$1") (pintype "passive"))
      (node (ref "C29") (pin "P$1") (pinfunction "P$1_P$1") (pintype "passive"))
      (node (ref "C30") (pin "P$1") (pinfunction "P$1_P$1") (pintype "passive"))
      (node (ref "C31") (pin "P$1") (pinfunction "P$1_P$1") (pintype "passive"))
      (node (ref "C33") (pin "P$1") (pinfunction "P$1_P$1") (pintype "passive"))
      (node (ref "C34") (pin "P$1") (pinfunction "P$1_P$1") (pintype "passive"))
      (node (ref "C35") (pin "P$1") (pinfunction "P$1_P$1") (pintype "passive"))
      (node (ref "C36") (pin "P$1") (pinfunction "P$1_P$1") (pintype "passive"))
      (node (ref "C37") (pin "P$1") (pinfunction "P$1_P$1") (pintype "passive"))
      (node (ref "C38") (pin "P$1") (pinfunction "P$1_P$1") (pintype "passive"))
      (node (ref "C39") (pin "P$1") (pinfunction "P$1_P$1") (pintype "passive"))
      (node (ref "C40") (pin "P$1") (pinfunction "P$1_P$1") (pintype "passive"))
      (node (ref "C41") (pin "P$1") (pinfunction "P$1_P$1") (pintype "passive"))
      (node (ref "J4") (pin "1") (pinfunction "1_1") (pintype "passive"))
      (node (ref "J4") (pin "17") (pinfunction "17_17") (pintype "passive"))
      (node (ref "JD1") (pin "6") (pinfunction "6_6") (pintype "passive"))
      (node (ref "JD2") (pin "6") (pinfunction "6_6") (pintype "passive"))
      (node (ref "JD3") (pin "6") (pinfunction "6_6") (pintype "passive"))
      (node (ref "L2") (pin "P$1") (pinfunction "P$1_P$1") (pintype "passive"))
      (node (ref "R11") (pin "P$1") (pinfunction "P$1_P$1") (pintype "passive"))
      (node (ref "R12") (pin "P$1") (pinfunction "P$1_P$1") (pintype "passive"))
      (node (ref "R14") (pin "P$1") (pinfunction "P$1_P$1") (pintype "passive"))
      (node (ref "R15") (pin "P$1") (pinfunction "P$1_P$1") (pintype "passive"))
      (node (ref "R16") (pin "P$1") (pinfunction "P$1_P$1") (pintype "passive"))
      (node (ref "R17") (pin "P$1") (pinfunction "P$1_P$1") (pintype "passive"))
      (node (ref "R18") (pin "P$1") (pinfunction "P$1_P$1") (pintype "passive"))
      (node (ref "R7") (pin "P$1") (pinfunction "P$1_P$1") (pintype "passive"))
      (node (ref "R8") (pin "P$1") (pinfunction "P$1_P$1") (pintype "passive"))
      (node (ref "U10") (pin "8") (pinfunction "VCC_8") (pintype "bidirectional"))
      (node (ref "U11") (pin "1") (pinfunction "VBAT_1") (pintype "bidirectional"))
      (node (ref "U11") (pin "20") (pinfunction "VREF+_20") (pintype "bidirectional"))
      (node (ref "U11") (pin "21") (pinfunction "VDDA_21") (pintype "bidirectional"))
      (node (ref "U11") (pin "23") (pinfunction "VDD_1_23") (pintype "bidirectional"))
      (node (ref "U11") (pin "35") (pinfunction "VDD_2_35") (pintype "bidirectional"))
      (node (ref "U11") (pin "4") (pinfunction "PC15-OSC32_OUT_4") (pintype "bidirectional"))
      (node (ref "U11") (pin "48") (pinfunction "VDD_3_48") (pintype "bidirectional"))
      (node (ref "U12") (pin "3") (pinfunction "VCC_3") (pintype "power_in"))
      (node (ref "U13") (pin "3") (pinfunction "VCC_3") (pintype "power_in"))
      (node (ref "U14") (pin "4") (pinfunction "VDD_4") (pintype "power_in"))
      (node (ref "U4") (pin "1") (pinfunction "VBAT_1") (pintype "bidirectional"))
      (node (ref "U4") (pin "20") (pinfunction "VREF+_20") (pintype "bidirectional"))
      (node (ref "U4") (pin "21") (pinfunction "VDDA_21") (pintype "bidirectional"))
      (node (ref "U4") (pin "23") (pinfunction "VDD_1_23") (pintype "bidirectional"))
      (node (ref "U4") (pin "35") (pinfunction "VDD_2_35") (pintype "bidirectional"))
      (node (ref "U4") (pin "48") (pinfunction "VDD_3_48") (pintype "bidirectional"))
      (node (ref "U5") (pin "3") (pinfunction "VCC_3") (pintype "power_in"))
      (node (ref "U6") (pin "3") (pinfunction "VCC_3") (pintype "power_in"))
      (node (ref "U7") (pin "1") (pinfunction "VBAT_1") (pintype "bidirectional"))
      (node (ref "U7") (pin "20") (pinfunction "VREF+_20") (pintype "bidirectional"))
      (node (ref "U7") (pin "21") (pinfunction "VDDA_21") (pintype "bidirectional"))
      (node (ref "U7") (pin "23") (pinfunction "VDD_1_23") (pintype "bidirectional"))
      (node (ref "U7") (pin "3") (pinfunction "PC14-OSC32_IN_3") (pintype "bidirectional"))
      (node (ref "U7") (pin "35") (pinfunction "VDD_2_35") (pintype "bidirectional"))
      (node (ref "U7") (pin "48") (pinfunction "VDD_3_48") (pintype "bidirectional"))
      (node (ref "U8") (pin "11") (pinfunction "VDDIO_11") (pintype "bidirectional"))
      (node (ref "U8") (pin "3") (pinfunction "VDD_3") (pintype "bidirectional"))
      (node (ref "U9") (pin "3") (pinfunction "VCC_3") (pintype "power_in"))
    )
    (net (code "2") (name "+5V") (class "Default")
      (node (ref "+5V") (pin "P$1") (pinfunction "P$1_P$1") (pintype "bidirectional"))
      (node (ref "J4") (pin "2") (pinfunction "2_2") (pintype "passive"))
      (node (ref "J4") (pin "4") (pinfunction "4_4") (pintype "passive"))
      (node (ref "R4") (pin "P$1") (pinfunction "P$1_P$1") (pintype "passive"))
      (node (ref "U2") (pin "6") (pinfunction "E1_6") (pintype "bidirectional"))
      (node (ref "U3") (pin "3") (pinfunction "D_3") (pintype "passive"))
    )
    (net (code "3") (name "/5VSW") (class "Default")
      (node (ref "C5") (pin "P$2") (pinfunction "P$2_P$2") (pintype "passive"))
      (node (ref "L1") (pin "1") (pinfunction "P$1_1") (pintype "passive"))
      (node (ref "U1") (pin "8") (pinfunction "SW_8") (pintype "bidirectional"))
    )
    (net (code "4") (name "/AUX_IRQ1") (class "Default")
      (node (ref "J4") (pin "15") (pinfunction "15_15") (pintype "passive"))
      (node (ref "U7") (pin "17") (pinfunction "PB0_17") (pintype "bidirectional"))
    )
    (net (code "5") (name "/AUX_IRQ2") (class "Default")
      (node (ref "J4") (pin "16") (pinfunction "16_16") (pintype "passive"))
      (node (ref "U7") (pin "18") (pinfunction "PB1_18") (pintype "bidirectional"))
    )
    (net (code "6") (name "/AUX_IRQ3") (class "Default")
      (node (ref "J4") (pin "18") (pinfunction "18_18") (pintype "passive"))
      (node (ref "U7") (pin "19") (pinfunction "PB2_19") (pintype "bidirectional"))
    )
    (net (code "7") (name "/CAN_SHDN") (class "Default")
      (node (ref "U7") (pin "29") (pinfunction "PC6_29") (pintype "bidirectional"))
      (node (ref "U9") (pin "8") (pinfunction "RS_8") (pintype "input"))
    )
    (net (code "8") (name "/I2C1_SCL") (class "Default")
      (node (ref "J4") (pin "5") (pinfunction "5_5") (pintype "passive"))
    )
    (net (code "9") (name "/I2C1_SDA") (class "Default")
      (node (ref "J4") (pin "3") (pinfunction "3_3") (pintype "passive"))
    )
    (net (code "10") (name "/ID_SCL") (class "Default")
      (node (ref "J4") (pin "28") (pinfunction "28_28") (pintype "passive"))
      (node (ref "R16") (pin "P$2") (pinfunction "P$2_P$2") (pintype "passive"))
      (node (ref "U10") (pin "6") (pinfunction "SCL_6") (pintype "bidirectional"))
    )
    (net (code "11") (name "/ID_SDA") (class "Default")
      (node (ref "J4") (pin "27") (pinfunction "27_27") (pintype "passive"))
      (node (ref "R15") (pin "P$2") (pinfunction "P$2_P$2") (pintype "passive"))
      (node (ref "U10") (pin "5") (pinfunction "SDA_5") (pintype "bidirectional"))
    )
    (net (code "12") (name "/IFACEA_IRQ1") (class "Default")
      (node (ref "J4") (pin "37") (pinfunction "37_37") (pintype "passive"))
      (node (ref "U4") (pin "17") (pinfunction "PB0_17") (pintype "bidirectional"))
    )
    (net (code "13") (name "/IFACEB_IRQ1") (class "Default")
      (node (ref "J4") (pin "29") (pinfunction "29_29") (pintype "passive"))
      (node (ref "U11") (pin "17") (pinfunction "PB0_17") (pintype "bidirectional"))
    )
    (net (code "14") (name "/IMU_ACC_INT") (class "Default")
      (node (ref "U7") (pin "32") (pinfunction "PA10_32") (pintype "bidirectional"))
      (node (ref "U8") (pin "16") (pinfunction "INT1_16") (pintype "bidirectional"))
    )
    (net (code "15") (name "/IMU_CS1") (class "Default")
      (node (ref "U7") (pin "31") (pinfunction "PA9_31") (pintype "bidirectional"))
      (node (ref "U8") (pin "14") (pinfunction "CSB1_14") (pintype "bidirectional"))
    )
    (net (code "16") (name "/IMU_CS2") (class "Default")
      (node (ref "U7") (pin "25") (pinfunction "PB12_25") (pintype "bidirectional"))
      (node (ref "U8") (pin "5") (pinfunction "CSB2_5") (pintype "bidirectional"))
    )
    (net (code "17") (name "/IMU_GYRO_INT") (class "Default")
      (node (ref "U7") (pin "30") (pinfunction "PA8_30") (pintype "bidirectional"))
      (node (ref "U8") (pin "12") (pinfunction "INT3_12") (pintype "bidirectional"))
    )
    (net (code "18") (name "/IMU_MISO") (class "Default")
      (node (ref "U7") (pin "27") (pinfunction "PB14_27") (pintype "bidirectional"))
      (node (ref "U8") (pin "10") (pinfunction "SDO2_10") (pintype "bidirectional"))
      (node (ref "U8") (pin "15") (pinfunction "SDO1_15") (pintype "bidirectional"))
    )
    (net (code "19") (name "/IMU_MOSI") (class "Default")
      (node (ref "U7") (pin "28") (pinfunction "PB15_28") (pintype "bidirectional"))
      (node (ref "U8") (pin "9") (pinfunction "SDI_9") (pintype "bidirectional"))
    )
    (net (code "20") (name "/IMU_SCK") (class "Default")
      (node (ref "U7") (pin "26") (pinfunction "PB13_26") (pintype "bidirectional"))
      (node (ref "U8") (pin "8") (pinfunction "SCK_8") (pintype "bidirectional"))
    )
    (net (code "21") (name "/MIC_IN") (class "Default")
      (node (ref "C42") (pin "P$2") (pinfunction "P$2_P$2") (pintype "passive"))
      (node (ref "U7") (pin "22") (pinfunction "PB10_22") (pintype "bidirectional"))
    )
    (net (code "22") (name "/NRF_CE") (class "Default")
      (node (ref "J3") (pin "6") (pinfunction "6_6") (pintype "passive"))
      (node (ref "U7") (pin "44") (pinfunction "PB6_44") (pintype "bidirectional"))
    )
    (net (code "23") (name "/NRF_CS") (class "Default")
      (node (ref "J3") (pin "5") (pinfunction "5_5") (pintype "passive"))
      (node (ref "U7") (pin "38") (pinfunction "PA15_38") (pintype "bidirectional"))
    )
    (net (code "24") (name "/NRF_IRQ") (class "Default")
      (node (ref "J3") (pin "1") (pinfunction "1_1") (pintype "passive"))
      (node (ref "U7") (pin "45") (pinfunction "PB7_45") (pintype "bidirectional"))
    )
    (net (code "25") (name "/NRF_MISO") (class "Default")
      (node (ref "J3") (pin "2") (pinfunction "2_2") (pintype "passive"))
      (node (ref "U7") (pin "42") (pinfunction "PB4_42") (pintype "bidirectional"))
    )
    (net (code "26") (name "/NRF_MOSI") (class "Default")
      (node (ref "J3") (pin "3") (pinfunction "3_3") (pintype "passive"))
      (node (ref "U7") (pin "43") (pinfunction "PB5_43") (pintype "bidirectional"))
    )
    (net (code "27") (name "/NRF_SCK") (class "Default")
      (node (ref "J3") (pin "4") (pinfunction "4_4") (pintype "passive"))
      (node (ref "U7") (pin "41") (pinfunction "PB3_41") (pintype "bidirectional"))
    )
    (net (code "28") (name "/PI32") (class "Default")
      (node (ref "J4") (pin "32") (pinfunction "32_32") (pintype "passive"))
      (node (ref "JP5") (pin "1") (pinfunction "1_1") (pintype "passive"))
    )
    (net (code "29") (name "/PI33") (class "Default")
      (node (ref "J4") (pin "33") (pinfunction "33_33") (pintype "passive"))
      (node (ref "JP5") (pin "2") (pinfunction "2_2") (pintype "passive"))
    )
    (net (code "30") (name "/PI_RX_3V") (class "Default")
      (node (ref "J4") (pin "10") (pinfunction "10_10") (pintype "passive"))
    )
    (net (code "31") (name "/PI_TX_3V") (class "Default")
      (node (ref "J4") (pin "8") (pinfunction "8_8") (pintype "passive"))
    )
    (net (code "32") (name "/REGOUT") (class "Default")
      (node (ref "C7") (pin "P$1") (pinfunction "P$1_P$1") (pintype "passive"))
      (node (ref "C8") (pin "P$1") (pinfunction "P$1_P$1") (pintype "passive"))
      (node (ref "L1") (pin "2") (pinfunction "P$2_2") (pintype "passive"))
      (node (ref "R2") (pin "P$1") (pinfunction "P$1_P$1") (pintype "passive"))
      (node (ref "REGOUT") (pin "P$1") (pinfunction "P$1_P$1") (pintype "bidirectional"))
      (node (ref "U2") (pin "5") (pinfunction "E2_5") (pintype "bidirectional"))
      (node (ref "U3") (pin "2") (pinfunction "S_2") (pintype "passive"))
    )
    (net (code "33") (name "/SPI0_CS0") (class "Default")
      (node (ref "J4") (pin "24") (pinfunction "24_24") (pintype "passive"))
      (node (ref "SPI0_CS0") (pin "P$1") (pinfunction "P$1_P$1") (pintype "bidirectional"))
      (node (ref "U7") (pin "12") (pinfunction "PA4_12") (pintype "bidirectional"))
    )
    (net (code "34") (name "/SPI0_CS1") (class "Default")
      (node (ref "J4") (pin "26") (pinfunction "26_26") (pintype "passive"))
    )
    (net (code "35") (name "/SPI0_MISO") (class "Default")
      (node (ref "J4") (pin "21") (pinfunction "21_21") (pintype "passive"))
      (node (ref "SPI0_MISO") (pin "P$1") (pinfunction "P$1_P$1") (pintype "bidirectional"))
      (node (ref "U7") (pin "14") (pinfunction "PA6_14") (pintype "bidirectional"))
    )
    (net (code "36") (name "/SPI0_MOSI") (class "Default")
      (node (ref "J4") (pin "19") (pinfunction "19_19") (pintype "passive"))
      (node (ref "SPI0_MOSI") (pin "P$1") (pinfunction "P$1_P$1") (pintype "bidirectional"))
      (node (ref "U7") (pin "15") (pinfunction "PA7_15") (pintype "bidirectional"))
    )
    (net (code "37") (name "/SPI0_SCLK") (class "Default")
      (node (ref "J4") (pin "23") (pinfunction "23_23") (pintype "passive"))
      (node (ref "SPI0_SCLK") (pin "P$1") (pinfunction "P$1_P$1") (pintype "bidirectional"))
      (node (ref "U7") (pin "13") (pinfunction "PA5_13") (pintype "bidirectional"))
    )
    (net (code "38") (name "/SPI1_CS0") (class "Default")
      (node (ref "J4") (pin "12") (pinfunction "12_12") (pintype "passive"))
      (node (ref "SPI1_CS0") (pin "P$1") (pinfunction "P$1_P$1") (pintype "bidirectional"))
      (node (ref "U4") (pin "12") (pinfunction "PA4_12") (pintype "bidirectional"))
    )
    (net (code "39") (name "/SPI1_CS1") (class "Default")
      (node (ref "J4") (pin "11") (pinfunction "11_11") (pintype "passive"))
      (node (ref "SPI1_CS1") (pin "P$1") (pinfunction "P$1_P$1") (pintype "bidirectional"))
      (node (ref "U11") (pin "12") (pinfunction "PA4_12") (pintype "bidirectional"))
    )
    (net (code "40") (name "/SPI1_CS2") (class "Default")
      (node (ref "J4") (pin "36") (pinfunction "36_36") (pintype "passive"))
    )
    (net (code "41") (name "/SPI1_MISO") (class "Default")
      (node (ref "J4") (pin "35") (pinfunction "35_35") (pintype "passive"))
      (node (ref "SPI1_MISO") (pin "P$1") (pinfunction "P$1_P$1") (pintype "bidirectional"))
      (node (ref "U11") (pin "14") (pinfunction "PA6_14") (pintype "bidirectional"))
      (node (ref "U4") (pin "14") (pinfunction "PA6_14") (pintype "bidirectional"))
    )
    (net (code "42") (name "/SPI1_MOSI") (class "Default")
      (node (ref "J4") (pin "38") (pinfunction "38_38") (pintype "passive"))
      (node (ref "SPI1_MOSI") (pin "P$1") (pinfunction "P$1_P$1") (pintype "bidirectional"))
      (node (ref "U11") (pin "15") (pinfunction "PA7_15") (pintype "bidirectional"))
      (node (ref "U4") (pin "15") (pinfunction "PA7_15") (pintype "bidirectional"))
    )
    (net (code "43") (name "/SPI1_SCLK") (class "Default")
      (node (ref "J4") (pin "40") (pinfunction "40_40") (pintype "passive"))
      (node (ref "SPI1_SCLK") (pin "P$1") (pinfunction "P$1_P$1") (pintype "bidirectional"))
      (node (ref "U11") (pin "13") (pinfunction "PA5_13") (pintype "bidirectional"))
      (node (ref "U4") (pin "13") (pinfunction "PA5_13") (pintype "bidirectional"))
    )
    (net (code "44") (name "/V+") (class "Default")
      (node (ref "F1") (pin "1") (pinfunction "1_1") (pintype "passive"))
      (node (ref "J1") (pin "2") (pinfunction "2_2") (pintype "passive"))
      (node (ref "J2") (pin "2") (pinfunction "2_2") (pintype "passive"))
      (node (ref "V+") (pin "P$1") (pinfunction "P$1_P$1") (pintype "bidirectional"))
    )
    (net (code "45") (name "/V+FUSED") (class "Default")
      (node (ref "C1") (pin "P$1") (pinfunction "P$1_P$1") (pintype "passive"))
      (node (ref "C2") (pin "P$1") (pinfunction "P$1_P$1") (pintype "passive"))
      (node (ref "C3") (pin "P$1") (pinfunction "P$1_P$1") (pintype "passive"))
      (node (ref "D8") (pin "C") (pinfunction "C_C") (pintype "bidirectional"))
      (node (ref "F1") (pin "2") (pinfunction "2_2") (pintype "passive"))
      (node (ref "U1") (pin "2") (pinfunction "VIN_2") (pintype "bidirectional"))
      (node (ref "U1") (pin "3") (pinfunction "EN_3") (pintype "bidirectional"))
    )
    (net (code "46") (name "GND") (class "Default")
      (node (ref "C1") (pin "P$2") (pinfunction "P$2_P$2") (pintype "passive"))
      (node (ref "C10") (pin "P$2") (pinfunction "P$2_P$2") (pintype "passive"))
      (node (ref "C11") (pin "P$2") (pinfunction "P$2_P$2") (pintype "passive"))
      (node (ref "C12") (pin "P$2") (pinfunction "P$2_P$2") (pintype "passive"))
      (node (ref "C13") (pin "P$2") (pinfunction "P$2_P$2") (pintype "passive"))
      (node (ref "C14") (pin "P$2") (pinfunction "P$2_P$2") (pintype "passive"))
      (node (ref "C15") (pin "P$2") (pinfunction "P$2_P$2") (pintype "passive"))
      (node (ref "C16") (pin "P$2") (pinfunction "P$2_P$2") (pintype "passive"))
      (node (ref "C17") (pin "P$2") (pinfunction "P$2_P$2") (pintype "passive"))
      (node (ref "C18") (pin "P$2") (pinfunction "P$2_P$2") (pintype "passive"))
      (node (ref "C19") (pin "P$2") (pinfunction "P$2_P$2") (pintype "passive"))
      (node (ref "C2") (pin "P$2") (pinfunction "P$2_P$2") (pintype "passive"))
      (node (ref "C20") (pin "P$2") (pinfunction "P$2_P$2") (pintype "passive"))
      (node (ref "C21") (pin "P$2") (pinfunction "P$2_P$2") (pintype "passive"))
      (node (ref "C22") (pin "P$2") (pinfunction "P$2_P$2") (pintype "passive"))
      (node (ref "C23") (pin "P$2") (pinfunction "P$2_P$2") (pintype "passive"))
      (node (ref "C24") (pin "P$2") (pinfunction "P$2_P$2") (pintype "passive"))
      (node (ref "C25") (pin "P$2") (pinfunction "P$2_P$2") (pintype "passive"))
      (node (ref "C26") (pin "P$2") (pinfunction "P$2_P$2") (pintype "passive"))
      (node (ref "C27") (pin "P$2") (pinfunction "P$2_P$2") (pintype "passive"))
      (node (ref "C28") (pin "P$2") (pinfunction "P$2_P$2") (pintype "passive"))
      (node (ref "C29") (pin "P$2") (pinfunction "P$2_P$2") (pintype "passive"))
      (node (ref "C3") (pin "P$2") (pinfunction "P$2_P$2") (pintype "passive"))
      (node (ref "C30") (pin "P$2") (pinfunction "P$2_P$2") (pintype "passive"))
      (node (ref "C31") (pin "P$2") (pinfunction "P$2_P$2") (pintype "passive"))
      (node (ref "C32") (pin "P$2") (pinfunction "P$2_P$2") (pintype "passive"))
      (node (ref "C33") (pin "P$2") (pinfunction "P$2_P$2") (pintype "passive"))
      (node (ref "C34") (pin "P$2") (pinfunction "P$2_P$2") (pintype "passive"))
      (node (ref "C35") (pin "P$2") (pinfunction "P$2_P$2") (pintype "passive"))
      (node (ref "C36") (pin "P$2") (pinfunction "P$2_P$2") (pintype "passive"))
      (node (ref "C37") (pin "P$2") (pinfunction "P$2_P$2") (pintype "passive"))
      (node (ref "C38") (pin "P$2") (pinfunction "P$2_P$2") (pintype "passive"))
      (node (ref "C39") (pin "P$2") (pinfunction "P$2_P$2") (pintype "passive"))
      (node (ref "C4") (pin "P$2") (pinfunction "P$2_P$2") (pintype "passive"))
      (node (ref "C40") (pin "P$2") (pinfunction "P$2_P$2") (pintype "passive"))
      (node (ref "C41") (pin "P$2") (pinfunction "P$2_P$2") (pintype "passive"))
      (node (ref "C43") (pin "P$2") (pinfunction "P$2_P$2") (pintype "passive"))
      (node (ref "C6") (pin "P$2") (pinfunction "P$2_P$2") (pintype "passive"))
      (node (ref "C7") (pin "P$2") (pinfunction "P$2_P$2") (pintype "passive"))
      (node (ref "C8") (pin "P$2") (pinfunction "P$2_P$2") (pintype "passive"))
      (node (ref "C9") (pin "P$2") (pinfunction "P$2_P$2") (pintype "passive"))
      (node (ref "D1") (pin "CATHODE") (pinfunction "CATHODE_CATHODE") (pintype "power_in"))
      (node (ref "D8") (pin "A") (pinfunction "A_A") (pintype "bidirectional"))
      (node (ref "GND") (pin "P$1") (pinfunction "P$1_P$1") (pintype "bidirectional"))
      (node (ref "J1") (pin "1") (pinfunction "1_1") (pintype "passive"))
      (node (ref "J2") (pin "1") (pinfunction "1_1") (pintype "passive"))
      (node (ref "J3") (pin "8") (pinfunction "8_8") (pintype "passive"))
      (node (ref "J4") (pin "14") (pinfunction "14_14") (pintype "passive"))
      (node (ref "J4") (pin "20") (pinfunction "20_20") (pintype "passive"))
      (node (ref "J4") (pin "25") (pinfunction "25_25") (pintype "passive"))
      (node (ref "J4") (pin "30") (pinfunction "30_30") (pintype "passive"))
      (node (ref "J4") (pin "34") (pinfunction "34_34") (pintype "passive"))
      (node (ref "J4") (pin "39") (pinfunction "39_39") (pintype "passive"))
      (node (ref "J4") (pin "6") (pinfunction "6_6") (pintype "passive"))
      (node (ref "J4") (pin "9") (pinfunction "9_9") (pintype "passive"))
      (node (ref "JC1") (pin "3") (pinfunction "3_3") (pintype "passive"))
      (node (ref "JC2") (pin "3") (pinfunction "3_3") (pintype "passive"))
      (node (ref "JC3") (pin "3") (pinfunction "3_3") (pintype "passive"))
      (node (ref "JC4") (pin "3") (pinfunction "3_3") (pintype "passive"))
      (node (ref "JC5") (pin "3") (pinfunction "3_3") (pintype "passive"))
      (node (ref "JD1") (pin "4") (pinfunction "4_4") (pintype "passive"))
      (node (ref "JD2") (pin "4") (pinfunction "4_4") (pintype "passive"))
      (node (ref "JD3") (pin "4") (pinfunction "4_4") (pintype "passive"))
      (node (ref "JP1") (pin "1") (pinfunction "1_1") (pintype "passive"))
      (node (ref "JP2") (pin "1") (pinfunction "1_1") (pintype "passive"))
      (node (ref "JP3") (pin "3") (pinfunction "3_3") (pintype "passive"))
      (node (ref "JP4") (pin "3") (pinfunction "3_3") (pintype "passive"))
      (node (ref "JP5") (pin "3") (pinfunction "3_3") (pintype "passive"))
      (node (ref "R3") (pin "P$2") (pinfunction "P$2_P$2") (pintype "passive"))
      (node (ref "R5") (pin "P$2") (pinfunction "P$2_P$2") (pintype "passive"))
      (node (ref "R6") (pin "P$2") (pinfunction "P$2_P$2") (pintype "passive"))
      (node (ref "U1") (pin "7") (pinfunction "GND_7") (pintype "bidirectional"))
      (node (ref "U1") (pin "P1") (pinfunction "GND_P1") (pintype "bidirectional"))
      (node (ref "U1") (pin "P2") (pinfunction "GND_P2") (pintype "bidirectional"))
      (node (ref "U1") (pin "P3") (pinfunction "GND_P3") (pintype "bidirectional"))
      (node (ref "U1") (pin "PAD") (pinfunction "GND_PAD") (pintype "bidirectional"))
      (node (ref "U10") (pin "1") (pinfunction "A0_1") (pintype "bidirectional"))
      (node (ref "U10") (pin "2") (pinfunction "A1_2") (pintype "bidirectional"))
      (node (ref "U10") (pin "3") (pinfunction "A2_3") (pintype "bidirectional"))
      (node (ref "U10") (pin "4") (pinfunction "VSS_4") (pintype "bidirectional"))
      (node (ref "U11") (pin "3") (pinfunction "PC14-OSC32_IN_3") (pintype "bidirectional"))
      (node (ref "U11") (pin "49") (pinfunction "THERMALPAD_49") (pintype "bidirectional"))
      (node (ref "U12") (pin "2") (pinfunction "GND_2") (pintype "power_in"))
      (node (ref "U12") (pin "5") (pinfunction "SHDN_5") (pintype "input"))
      (node (ref "U12") (pin "8") (pinfunction "STB_8") (pintype "input"))
      (node (ref "U13") (pin "2") (pinfunction "GND_2") (pintype "power_in"))
      (node (ref "U13") (pin "5") (pinfunction "SHDN_5") (pintype "input"))
      (node (ref "U13") (pin "8") (pinfunction "STB_8") (pintype "input"))
      (node (ref "U14") (pin "2") (pinfunction "GND_2") (pintype "power_in"))
      (node (ref "U14") (pin "3") (pinfunction "GND_3") (pintype "power_in"))
      (node (ref "U4") (pin "3") (pinfunction "PC14-OSC32_IN_3") (pintype "bidirectional"))
      (node (ref "U4") (pin "4") (pinfunction "PC15-OSC32_OUT_4") (pintype "bidirectional"))
      (node (ref "U4") (pin "49") (pinfunction "THERMALPAD_49") (pintype "bidirectional"))
      (node (ref "U5") (pin "2") (pinfunction "GND_2") (pintype "power_in"))
      (node (ref "U5") (pin "5") (pinfunction "SHDN_5") (pintype "input"))
      (node (ref "U5") (pin "8") (pinfunction "STB_8") (pintype "input"))
      (node (ref "U6") (pin "2") (pinfunction "GND_2") (pintype "power_in"))
      (node (ref "U6") (pin "5") (pinfunction "SHDN_5") (pintype "input"))
      (node (ref "U6") (pin "8") (pinfunction "STB_8") (pintype "input"))
      (node (ref "U7") (pin "4") (pinfunction "PC15-OSC32_OUT_4") (pintype "bidirectional"))
      (node (ref "U7") (pin "49") (pinfunction "THERMALPAD_49") (pintype "bidirectional"))
      (node (ref "U8") (pin "4") (pinfunction "GND_4") (pintype "bidirectional"))
      (node (ref "U8") (pin "6") (pinfunction "GNDIO_6") (pintype "bidirectional"))
      (node (ref "U8") (pin "7") (pinfunction "PS_7") (pintype "bidirectional"))
      (node (ref "U9") (pin "2") (pinfunction "GND_2") (pintype "power_in"))
    )
    (net (code "47") (name "Net-(C6-PadP$1)") (class "Default")
      (node (ref "C6") (pin "P$1") (pinfunction "P$1_P$1") (pintype "passive"))
      (node (ref "R1") (pin "P$2") (pinfunction "P$2_P$2") (pintype "passive"))
    )
    (net (code "48") (name "Net-(C26-PadP$1)") (class "Default")
      (node (ref "C26") (pin "P$1") (pinfunction "P$1_P$1") (pintype "passive"))
      (node (ref "C43") (pin "P$1") (pinfunction "P$1_P$1") (pintype "passive"))
      (node (ref "J3") (pin "7") (pinfunction "7_7") (pintype "passive"))
      (node (ref "L2") (pin "P$2") (pinfunction "P$2_P$2") (pintype "passive"))
    )
    (net (code "49") (name "Net-(D1-PadANODE)") (class "Default")
      (node (ref "D1") (pin "ANODE") (pinfunction "ANODE_ANODE") (pintype "power_in"))
      (node (ref "R4") (pin "P$2") (pinfunction "P$2_P$2") (pintype "passive"))
    )
    (net (code "50") (name "Net-(D2-PadANODE)") (class "Default")
      (node (ref "D2") (pin "ANODE") (pinfunction "ANODE_ANODE") (pintype "power_in"))
      (node (ref "R7") (pin "P$2") (pinfunction "P$2_P$2") (pintype "passive"))
    )
    (net (code "51") (name "Net-(D3-PadANODE)") (class "Default")
      (node (ref "D3") (pin "ANODE") (pinfunction "ANODE_ANODE") (pintype "power_in"))
      (node (ref "R8") (pin "P$2") (pinfunction "P$2_P$2") (pintype "passive"))
    )
    (net (code "52") (name "Net-(D4-PadANODE)") (class "Default")
      (node (ref "D4") (pin "ANODE") (pinfunction "ANODE_ANODE") (pintype "power_in"))
      (node (ref "R11") (pin "P$2") (pinfunction "P$2_P$2") (pintype "passive"))
    )
    (net (code "53") (name "Net-(D5-PadANODE)") (class "Default")
      (node (ref "D5") (pin "ANODE") (pinfunction "ANODE_ANODE") (pintype "power_in"))
      (node (ref "R12") (pin "P$2") (pinfunction "P$2_P$2") (pintype "passive"))
    )
    (net (code "54") (name "Net-(D6-PadANODE)") (class "Default")
      (node (ref "D6") (pin "ANODE") (pinfunction "ANODE_ANODE") (pintype "power_in"))
      (node (ref "R17") (pin "P$2") (pinfunction "P$2_P$2") (pintype "passive"))
    )
    (net (code "55") (name "Net-(D7-PadANODE)") (class "Default")
      (node (ref "D7") (pin "ANODE") (pinfunction "ANODE_ANODE") (pintype "power_in"))
      (node (ref "R18") (pin "P$2") (pinfunction "P$2_P$2") (pintype "passive"))
    )
    (net (code "56") (name "Net-(U1-BST)") (class "Default")
      (node (ref "C5") (pin "P$1") (pinfunction "P$1_P$1") (pintype "passive"))
      (node (ref "U1") (pin "1") (pinfunction "BST_1") (pintype "bidirectional"))
    )
    (net (code "57") (name "Net-(U1-COMP)") (class "Default")
      (node (ref "R1") (pin "P$1") (pinfunction "P$1_P$1") (pintype "passive"))
      (node (ref "U1") (pin "6") (pinfunction "COMP_6") (pintype "bidirectional"))
    )
    (net (code "58") (name "Net-(U1-FB)") (class "Default")
      (node (ref "R2") (pin "P$2") (pinfunction "P$2_P$2") (pintype "passive"))
      (node (ref "R3") (pin "P$1") (pinfunction "P$1_P$1") (pintype "passive"))
      (node (ref "U1") (pin "5") (pinfunction "FB_5") (pintype "bidirectional"))
    )
    (net (code "59") (name "Net-(U1-SS)") (class "Default")
      (node (ref "C4") (pin "P$1") (pinfunction "P$1_P$1") (pintype "passive"))
      (node (ref "U1") (pin "4") (pinfunction "SS_4") (pintype "bidirectional"))
    )
    (net (code "60") (name "Net-(U2-B1)") (class "Default")
      (node (ref "R5") (pin "P$1") (pinfunction "P$1_P$1") (pintype "passive"))
      (node (ref "U2") (pin "2") (pinfunction "B1_2") (pintype "bidirectional"))
      (node (ref "U2") (pin "3") (pinfunction "B2_3") (pintype "bidirectional"))
      (node (ref "U2") (pin "4") (pinfunction "C2_4") (pintype "bidirectional"))
    )
    (net (code "61") (name "Net-(U2-C1)") (class "Default")
      (node (ref "R6") (pin "P$1") (pinfunction "P$1_P$1") (pintype "passive"))
      (node (ref "U2") (pin "1") (pinfunction "C1_1") (pintype "bidirectional"))
      (node (ref "U3") (pin "1") (pinfunction "G_1") (pintype "passive"))
    )
    (net (code "62") (name "Net-(U4-PA11)") (class "Default")
      (node (ref "U4") (pin "33") (pinfunction "PA11_33") (pintype "bidirectional"))
      (node (ref "U6") (pin "4") (pinfunction "RXD_4") (pintype "output"))
    )
    (net (code "63") (name "Net-(U4-PA12)") (class "Default")
      (node (ref "U4") (pin "34") (pinfunction "PA12_34") (pintype "bidirectional"))
      (node (ref "U6") (pin "1") (pinfunction "TXD_1") (pintype "input"))
    )
    (net (code "64") (name "Net-(U4-PA13)") (class "Default")
      (node (ref "JD1") (pin "3") (pinfunction "3_3") (pintype "passive"))
      (node (ref "U4") (pin "36") (pinfunction "PA13_36") (pintype "bidirectional"))
    )
    (net (code "65") (name "Net-(U4-PA14)") (class "Default")
      (node (ref "JD1") (pin "5") (pinfunction "5_5") (pintype "passive"))
      (node (ref "U4") (pin "37") (pinfunction "PA14_37") (pintype "bidirectional"))
    )
    (net (code "66") (name "Net-(U4-PB3)") (class "Default")
      (node (ref "U4") (pin "41") (pinfunction "PB3_41") (pintype "bidirectional"))
      (node (ref "U5") (pin "4") (pinfunction "RXD_4") (pintype "output"))
    )
    (net (code "67") (name "Net-(U4-PB4)") (class "Default")
      (node (ref "U4") (pin "42") (pinfunction "PB4_42") (pintype "bidirectional"))
      (node (ref "U5") (pin "1") (pinfunction "TXD_1") (pintype "input"))
    )
    (net (code "68") (name "Net-(U4-PB12)") (class "Default")
      (node (ref "JP4") (pin "2") (pinfunction "2_2") (pintype "passive"))
      (node (ref "U4") (pin "25") (pinfunction "PB12_25") (pintype "bidirectional"))
    )
    (net (code "69") (name "Net-(U4-PB13)") (class "Default")
      (node (ref "JP4") (pin "1") (pinfunction "1_1") (pintype "passive"))
      (node (ref "U4") (pin "26") (pinfunction "PB13_26") (pintype "bidirectional"))
    )
    (net (code "70") (name "Net-(U4-PF0-OSC_IN)") (class "Default")
      (node (ref "D3") (pin "CATHODE") (pinfunction "CATHODE_CATHODE") (pintype "power_in"))
      (node (ref "U4") (pin "5") (pinfunction "PF0-OSC_IN_5") (pintype "bidirectional"))
    )
    (net (code "71") (name "Net-(U4-PF1-OSC_OUT)") (class "Default")
      (node (ref "D2") (pin "CATHODE") (pinfunction "CATHODE_CATHODE") (pintype "power_in"))
      (node (ref "U4") (pin "6") (pinfunction "PF1-OSC_OUT_6") (pintype "bidirectional"))
    )
    (net (code "72") (name "Net-(U4-PG10-NRST)") (class "Default")
      (node (ref "C9") (pin "P$1") (pinfunction "P$1_P$1") (pintype "passive"))
      (node (ref "JD1") (pin "2") (pinfunction "2_2") (pintype "passive"))
      (node (ref "U4") (pin "7") (pinfunction "PG10-NRST_7") (pintype "bidirectional"))
    )
    (net (code "73") (name "Net-(U5-CANH)") (class "Default")
      (node (ref "JC1") (pin "1") (pinfunction "1_1") (pintype "passive"))
      (node (ref "R9") (pin "P$1") (pinfunction "P$1_P$1") (pintype "passive"))
      (node (ref "U5") (pin "7") (pinfunction "CANH_7") (pintype "bidirectional"))
    )
    (net (code "74") (name "Net-(U5-CANL)") (class "Default")
      (node (ref "JC1") (pin "2") (pinfunction "2_2") (pintype "passive"))
      (node (ref "R9") (pin "P$2") (pinfunction "P$2_P$2") (pintype "passive"))
      (node (ref "U5") (pin "6") (pinfunction "CANL_6") (pintype "bidirectional"))
    )
    (net (code "75") (name "Net-(U6-CANH)") (class "Default")
      (node (ref "JC2") (pin "1") (pinfunction "1_1") (pintype "passive"))
      (node (ref "R10") (pin "P$1") (pinfunction "P$1_P$1") (pintype "passive"))
      (node (ref "U6") (pin "7") (pinfunction "CANH_7") (pintype "bidirectional"))
    )
    (net (code "76") (name "Net-(U6-CANL)") (class "Default")
      (node (ref "JC2") (pin "2") (pinfunction "2_2") (pintype "passive"))
      (node (ref "R10") (pin "P$2") (pinfunction "P$2_P$2") (pintype "passive"))
      (node (ref "U6") (pin "6") (pinfunction "CANL_6") (pintype "bidirectional"))
    )
    (net (code "77") (name "Net-(U7-PA0)") (class "Default")
      (node (ref "JP2") (pin "5") (pinfunction "5_5") (pintype "passive"))
      (node (ref "U7") (pin "8") (pinfunction "PA0_8") (pintype "bidirectional"))
    )
    (net (code "78") (name "Net-(U7-PA1)") (class "Default")
      (node (ref "JP2") (pin "4") (pinfunction "4_4") (pintype "passive"))
      (node (ref "U7") (pin "9") (pinfunction "PA1_9") (pintype "bidirectional"))
    )
    (net (code "79") (name "Net-(U7-PA2)") (class "Default")
      (node (ref "JP2") (pin "3") (pinfunction "3_3") (pintype "passive"))
      (node (ref "U7") (pin "10") (pinfunction "PA2_10") (pintype "bidirectional"))
    )
    (net (code "80") (name "Net-(U7-PA3)") (class "Default")
      (node (ref "JP2") (pin "2") (pinfunction "2_2") (pintype "passive"))
      (node (ref "U7") (pin "11") (pinfunction "PA3_11") (pintype "bidirectional"))
    )
    (net (code "81") (name "Net-(U7-PA11)") (class "Default")
      (node (ref "U7") (pin "33") (pinfunction "PA11_33") (pintype "bidirectional"))
      (node (ref "U9") (pin "4") (pinfunction "RXD_4") (pintype "output"))
    )
    (net (code "82") (name "Net-(U7-PA12)") (class "Default")
      (node (ref "U7") (pin "34") (pinfunction "PA12_34") (pintype "bidirectional"))
      (node (ref "U9") (pin "1") (pinfunction "TXD_1") (pintype "input"))
    )
    (net (code "83") (name "Net-(U7-PA13)") (class "Default")
      (node (ref "JD3") (pin "3") (pinfunction "3_3") (pintype "passive"))
      (node (ref "U7") (pin "36") (pinfunction "PA13_36") (pintype "bidirectional"))
    )
    (net (code "84") (name "Net-(U7-PA14)") (class "Default")
      (node (ref "JD3") (pin "5") (pinfunction "5_5") (pintype "passive"))
      (node (ref "U7") (pin "37") (pinfunction "PA14_37") (pintype "bidirectional"))
    )
    (net (code "85") (name "Net-(U7-PF0-OSC_IN)") (class "Default")
      (node (ref "D5") (pin "CATHODE") (pinfunction "CATHODE_CATHODE") (pintype "power_in"))
      (node (ref "U7") (pin "5") (pinfunction "PF0-OSC_IN_5") (pintype "bidirectional"))
    )
    (net (code "86") (name "Net-(U7-PF1-OSC_OUT)") (class "Default")
      (node (ref "D4") (pin "CATHODE") (pinfunction "CATHODE_CATHODE") (pintype "power_in"))
      (node (ref "U7") (pin "6") (pinfunction "PF1-OSC_OUT_6") (pintype "bidirectional"))
    )
    (net (code "87") (name "Net-(U7-PG10-NRST)") (class "Default")
      (node (ref "C18") (pin "P$1") (pinfunction "P$1_P$1") (pintype "passive"))
      (node (ref "JD3") (pin "2") (pinfunction "2_2") (pintype "passive"))
      (node (ref "U7") (pin "7") (pinfunction "PG10-NRST_7") (pintype "bidirectional"))
    )
    (net (code "88") (name "Net-(U9-CANH)") (class "Default")
      (node (ref "JC5") (pin "1") (pinfunction "1_1") (pintype "passive"))
      (node (ref "R13") (pin "P$1") (pinfunction "P$1_P$1") (pintype "passive"))
      (node (ref "U9") (pin "7") (pinfunction "CANH_7") (pintype "bidirectional"))
    )
    (net (code "89") (name "Net-(U9-CANL)") (class "Default")
      (node (ref "JC5") (pin "2") (pinfunction "2_2") (pintype "passive"))
      (node (ref "R13") (pin "P$2") (pinfunction "P$2_P$2") (pintype "passive"))
      (node (ref "U9") (pin "6") (pinfunction "CANL_6") (pintype "bidirectional"))
    )
    (net (code "90") (name "Net-(U10-WP)") (class "Default")
      (node (ref "JP1") (pin "2") (pinfunction "2_2") (pintype "passive"))
      (node (ref "R14") (pin "P$2") (pinfunction "P$2_P$2") (pintype "passive"))
      (node (ref "U10") (pin "7") (pinfunction "WP_7") (pintype "bidirectional"))
    )
    (net (code "91") (name "Net-(U11-PA11)") (class "Default")
      (node (ref "U11") (pin "33") (pinfunction "PA11_33") (pintype "bidirectional"))
      (node (ref "U13") (pin "4") (pinfunction "RXD_4") (pintype "output"))
    )
    (net (code "92") (name "Net-(U11-PA12)") (class "Default")
      (node (ref "U11") (pin "34") (pinfunction "PA12_34") (pintype "bidirectional"))
      (node (ref "U13") (pin "1") (pinfunction "TXD_1") (pintype "input"))
    )
    (net (code "93") (name "Net-(U11-PA13)") (class "Default")
      (node (ref "JD2") (pin "3") (pinfunction "3_3") (pintype "passive"))
      (node (ref "U11") (pin "36") (pinfunction "PA13_36") (pintype "bidirectional"))
    )
    (net (code "94") (name "Net-(U11-PA14)") (class "Default")
      (node (ref "JD2") (pin "5") (pinfunction "5_5") (pintype "passive"))
      (node (ref "U11") (pin "37") (pinfunction "PA14_37") (pintype "bidirectional"))
    )
    (net (code "95") (name "Net-(U11-PB3)") (class "Default")
      (node (ref "U11") (pin "41") (pinfunction "PB3_41") (pintype "bidirectional"))
      (node (ref "U12") (pin "4") (pinfunction "RXD_4") (pintype "output"))
    )
    (net (code "96") (name "Net-(U11-PB4)") (class "Default")
      (node (ref "U11") (pin "42") (pinfunction "PB4_42") (pintype "bidirectional"))
      (node (ref "U12") (pin "1") (pinfunction "TXD_1") (pintype "input"))
    )
    (net (code "97") (name "Net-(U11-PB12)") (class "Default")
      (node (ref "JP3") (pin "2") (pinfunction "2_2") (pintype "passive"))
      (node (ref "U11") (pin "25") (pinfunction "PB12_25") (pintype "bidirectional"))
    )
    (net (code "98") (name "Net-(U11-PB13)") (class "Default")
      (node (ref "JP3") (pin "1") (pinfunction "1_1") (pintype "passive"))
      (node (ref "U11") (pin "26") (pinfunction "PB13_26") (pintype "bidirectional"))
    )
    (net (code "99") (name "Net-(U11-PF0-OSC_IN)") (class "Default")
      (node (ref "D7") (pin "CATHODE") (pinfunction "CATHODE_CATHODE") (pintype "power_in"))
      (node (ref "U11") (pin "5") (pinfunction "PF0-OSC_IN_5") (pintype "bidirectional"))
    )
    (net (code "100") (name "Net-(U11-PF1-OSC_OUT)") (class "Default")
      (node (ref "D6") (pin "CATHODE") (pinfunction "CATHODE_CATHODE") (pintype "power_in"))
      (node (ref "U11") (pin "6") (pinfunction "PF1-OSC_OUT_6") (pintype "bidirectional"))
    )
    (net (code "101") (name "Net-(U11-PG10-NRST)") (class "Default")
      (node (ref "C32") (pin "P$1") (pinfunction "P$1_P$1") (pintype "passive"))
      (node (ref "JD2") (pin "2") (pinfunction "2_2") (pintype "passive"))
      (node (ref "U11") (pin "7") (pinfunction "PG10-NRST_7") (pintype "bidirectional"))
    )
    (net (code "102") (name "Net-(U12-CANH)") (class "Default")
      (node (ref "JC3") (pin "1") (pinfunction "1_1") (pintype "passive"))
      (node (ref "R19") (pin "P$1") (pinfunction "P$1_P$1") (pintype "passive"))
      (node (ref "U12") (pin "7") (pinfunction "CANH_7") (pintype "bidirectional"))
    )
    (net (code "103") (name "Net-(U12-CANL)") (class "Default")
      (node (ref "JC3") (pin "2") (pinfunction "2_2") (pintype "passive"))
      (node (ref "R19") (pin "P$2") (pinfunction "P$2_P$2") (pintype "passive"))
      (node (ref "U12") (pin "6") (pinfunction "CANL_6") (pintype "bidirectional"))
    )
    (net (code "104") (name "Net-(U13-CANH)") (class "Default")
      (node (ref "JC4") (pin "1") (pinfunction "1_1") (pintype "passive"))
      (node (ref "R20") (pin "P$1") (pinfunction "P$1_P$1") (pintype "passive"))
      (node (ref "U13") (pin "7") (pinfunction "CANH_7") (pintype "bidirectional"))
    )
    (net (code "105") (name "Net-(U13-CANL)") (class "Default")
      (node (ref "JC4") (pin "2") (pinfunction "2_2") (pintype "passive"))
      (node (ref "R20") (pin "P$2") (pinfunction "P$2_P$2") (pintype "passive"))
      (node (ref "U13") (pin "6") (pinfunction "CANL_6") (pintype "bidirectional"))
    )
    (net (code "106") (name "Net-(U14-OUTPUT)") (class "Default")
      (node (ref "C42") (pin "P$1") (pinfunction "P$1_P$1") (pintype "passive"))
      (node (ref "U14") (pin "1") (pinfunction "OUTPUT_1") (pintype "output"))
    )
    (net (code "107") (name "unconnected-(J4-Pad7)") (class "Default")
      (node (ref "J4") (pin "7") (pinfunction "7_7") (pintype "passive"))
    )
    (net (code "108") (name "unconnected-(J4-Pad13)") (class "Default")
      (node (ref "J4") (pin "13") (pinfunction "13_13") (pintype "passive"))
    )
    (net (code "109") (name "unconnected-(J4-Pad22)") (class "Default")
      (node (ref "J4") (pin "22") (pinfunction "22_22") (pintype "passive"))
    )
    (net (code "110") (name "unconnected-(J4-Pad31)") (class "Default")
      (node (ref "J4") (pin "31") (pinfunction "31_31") (pintype "passive"))
    )
    (net (code "111") (name "unconnected-(JD1-Pad1)") (class "Default")
      (node (ref "JD1") (pin "1") (pinfunction "1_1") (pintype "passive"))
    )
    (net (code "112") (name "unconnected-(JD2-Pad1)") (class "Default")
      (node (ref "JD2") (pin "1") (pinfunction "1_1") (pintype "passive"))
    )
    (net (code "113") (name "unconnected-(JD3-Pad1)") (class "Default")
      (node (ref "JD3") (pin "1") (pinfunction "1_1") (pintype "passive"))
    )
    (net (code "114") (name "unconnected-(U4-PA0-Pad8)") (class "Default")
      (node (ref "U4") (pin "8") (pinfunction "PA0_8") (pintype "bidirectional"))
    )
    (net (code "115") (name "unconnected-(U4-PA1-Pad9)") (class "Default")
      (node (ref "U4") (pin "9") (pinfunction "PA1_9") (pintype "bidirectional"))
    )
    (net (code "116") (name "unconnected-(U4-PA2-Pad10)") (class "Default")
      (node (ref "U4") (pin "10") (pinfunction "PA2_10") (pintype "bidirectional"))
    )
    (net (code "117") (name "unconnected-(U4-PA3-Pad11)") (class "Default")
      (node (ref "U4") (pin "11") (pinfunction "PA3_11") (pintype "bidirectional"))
    )
    (net (code "118") (name "unconnected-(U4-PA8-Pad30)") (class "Default")
      (node (ref "U4") (pin "30") (pinfunction "PA8_30") (pintype "bidirectional"))
    )
    (net (code "119") (name "unconnected-(U4-PA9-Pad31)") (class "Default")
      (node (ref "U4") (pin "31") (pinfunction "PA9_31") (pintype "bidirectional"))
    )
    (net (code "120") (name "unconnected-(U4-PA10-Pad32)") (class "Default")
      (node (ref "U4") (pin "32") (pinfunction "PA10_32") (pintype "bidirectional"))
    )
    (net (code "121") (name "unconnected-(U4-PA15-Pad38)") (class "Default")
      (node (ref "U4") (pin "38") (pinfunction "PA15_38") (pintype "bidirectional"))
    )
    (net (code "122") (name "unconnected-(U4-PB1-Pad18)") (class "Default")
      (node (ref "U4") (pin "18") (pinfunction "PB1_18") (pintype "bidirectional"))
    )
    (net (code "123") (name "unconnected-(U4-PB2-Pad19)") (class "Default")
      (node (ref "U4") (pin "19") (pinfunction "PB2_19") (pintype "bidirectional"))
    )
    (net (code "124") (name "unconnected-(U4-PB5-Pad43)") (class "Default")
      (node (ref "U4") (pin "43") (pinfunction "PB5_43") (pintype "bidirectional"))
    )
    (net (code "125") (name "unconnected-(U4-PB6-Pad44)") (class "Default")
      (node (ref "U4") (pin "44") (pinfunction "PB6_44") (pintype "bidirectional"))
    )
    (net (code "126") (name "unconnected-(U4-PB7-Pad45)") (class "Default")
      (node (ref "U4") (pin "45") (pinfunction "PB7_45") (pintype "bidirectional"))
    )
    (net (code "127") (name "unconnected-(U4-PB8-BOOT0-Pad46)") (class "Default")
      (node (ref "U4") (pin "46") (pinfunction "PB8-BOOT0_46") (pintype "bidirectional"))
    )
    (net (code "128") (name "unconnected-(U4-PB9-Pad47)") (class "Default")
      (node (ref "U4") (pin "47") (pinfunction "PB9_47") (pintype "bidirectional"))
    )
    (net (code "129") (name "unconnected-(U4-PB10-Pad22)") (class "Default")
      (node (ref "U4") (pin "22") (pinfunction "PB10_22") (pintype "bidirectional"))
    )
    (net (code "130") (name "unconnected-(U4-PB11-Pad24)") (class "Default")
      (node (ref "U4") (pin "24") (pinfunction "PB11_24") (pintype "bidirectional"))
    )
    (net (code "131") (name "unconnected-(U4-PB14-Pad27)") (class "Default")
      (node (ref "U4") (pin "27") (pinfunction "PB14_27") (pintype "bidirectional"))
    )
    (net (code "132") (name "unconnected-(U4-PB15-Pad28)") (class "Default")
      (node (ref "U4") (pin "28") (pinfunction "PB15_28") (pintype "bidirectional"))
    )
    (net (code "133") (name "unconnected-(U4-PC4-Pad16)") (class "Default")
      (node (ref "U4") (pin "16") (pinfunction "PC4_16") (pintype "bidirectional"))
    )
    (net (code "134") (name "unconnected-(U4-PC6-Pad29)") (class "Default")
      (node (ref "U4") (pin "29") (pinfunction "PC6_29") (pintype "bidirectional"))
    )
    (net (code "135") (name "unconnected-(U4-PC10-Pad39)") (class "Default")
      (node (ref "U4") (pin "39") (pinfunction "PC10_39") (pintype "bidirectional"))
    )
    (net (code "136") (name "unconnected-(U4-PC11-Pad40)") (class "Default")
      (node (ref "U4") (pin "40") (pinfunction "PC11_40") (pintype "bidirectional"))
    )
    (net (code "137") (name "unconnected-(U4-PC13-Pad2)") (class "Default")
      (node (ref "U4") (pin "2") (pinfunction "PC13_2") (pintype "bidirectional"))
    )
    (net (code "138") (name "unconnected-(U7-PB8-BOOT0-Pad46)") (class "Default")
      (node (ref "U7") (pin "46") (pinfunction "PB8-BOOT0_46") (pintype "bidirectional"))
    )
    (net (code "139") (name "unconnected-(U7-PB9-Pad47)") (class "Default")
      (node (ref "U7") (pin "47") (pinfunction "PB9_47") (pintype "bidirectional"))
    )
    (net (code "140") (name "unconnected-(U7-PB11-Pad24)") (class "Default")
      (node (ref "U7") (pin "24") (pinfunction "PB11_24") (pintype "bidirectional"))
    )
    (net (code "141") (name "unconnected-(U7-PC4-Pad16)") (class "Default")
      (node (ref "U7") (pin "16") (pinfunction "PC4_16") (pintype "bidirectional"))
    )
    (net (code "142") (name "unconnected-(U7-PC10-Pad39)") (class "Default")
      (node (ref "U7") (pin "39") (pinfunction "PC10_39") (pintype "bidirectional"))
    )
    (net (code "143") (name "unconnected-(U7-PC11-Pad40)") (class "Default")
      (node (ref "U7") (pin "40") (pinfunction "PC11_40") (pintype "bidirectional"))
    )
    (net (code "144") (name "unconnected-(U7-PC13-Pad2)") (class "Default")
      (node (ref "U7") (pin "2") (pinfunction "PC13_2") (pintype "bidirectional"))
    )
    (net (code "145") (name "unconnected-(U8-INT2-Pad1)") (class "Default")
      (node (ref "U8") (pin "1") (pinfunction "INT2_1") (pintype "bidirectional"))
    )
    (net (code "146") (name "unconnected-(U8-INT4-Pad13)") (class "Default")
      (node (ref "U8") (pin "13") (pinfunction "INT4_13") (pintype "bidirectional"))
    )
    (net (code "147") (name "unconnected-(U8-NC-Pad2)") (class "Default")
      (node (ref "U8") (pin "2") (pinfunction "NC_2") (pintype "bidirectional"))
    )
    (net (code "148") (name "unconnected-(U9-SPLIT-Pad5)") (class "Default")
      (node (ref "U9") (pin "5") (pinfunction "SPLIT_5") (pintype "input"))
    )
    (net (code "149") (name "unconnected-(U11-PA0-Pad8)") (class "Default")
      (node (ref "U11") (pin "8") (pinfunction "PA0_8") (pintype "bidirectional"))
    )
    (net (code "150") (name "unconnected-(U11-PA1-Pad9)") (class "Default")
      (node (ref "U11") (pin "9") (pinfunction "PA1_9") (pintype "bidirectional"))
    )
    (net (code "151") (name "unconnected-(U11-PA2-Pad10)") (class "Default")
      (node (ref "U11") (pin "10") (pinfunction "PA2_10") (pintype "bidirectional"))
    )
    (net (code "152") (name "unconnected-(U11-PA3-Pad11)") (class "Default")
      (node (ref "U11") (pin "11") (pinfunction "PA3_11") (pintype "bidirectional"))
    )
    (net (code "153") (name "unconnected-(U11-PA8-Pad30)") (class "Default")
      (node (ref "U11") (pin "30") (pinfunction "PA8_30") (pintype "bidirectional"))
    )
    (net (code "154") (name "unconnected-(U11-PA9-Pad31)") (class "Default")
      (node (ref "U11") (pin "31") (pinfunction "PA9_31") (pintype "bidirectional"))
    )
    (net (code "155") (name "unconnected-(U11-PA10-Pad32)") (class "Default")
      (node (ref "U11") (pin "32") (pinfunction "PA10_32") (pintype "bidirectional"))
    )
    (net (code "156") (name "unconnected-(U11-PA15-Pad38)") (class "Default")
      (node (ref "U11") (pin "38") (pinfunction "PA15_38") (pintype "bidirectional"))
    )
    (net (code "157") (name "unconnected-(U11-PB1-Pad18)") (class "Default")
      (node (ref "U11") (pin "18") (pinfunction "PB1_18") (pintype "bidirectional"))
    )
    (net (code "158") (name "unconnected-(U11-PB2-Pad19)") (class "Default")
      (node (ref "U11") (pin "19") (pinfunction "PB2_19") (pintype "bidirectional"))
    )
    (net (code "159") (name "unconnected-(U11-PB5-Pad43)") (class "Default")
      (node (ref "U11") (pin "43") (pinfunction "PB5_43") (pintype "bidirectional"))
    )
    (net (code "160") (name "unconnected-(U11-PB6-Pad44)") (class "Default")
      (node (ref "U11") (pin "44") (pinfunction "PB6_44") (pintype "bidirectional"))
    )
    (net (code "161") (name "unconnected-(U11-PB7-Pad45)") (class "Default")
      (node (ref "U11") (pin "45") (pinfunction "PB7_45") (pintype "bidirectional"))
    )
    (net (code "162") (name "unconnected-(U11-PB8-BOOT0-Pad46)") (class "Default")
      (node (ref "U11") (pin "46") (pinfunction "PB8-BOOT0_46") (pintype "bidirectional"))
    )
    (net (code "163") (name "unconnected-(U11-PB9-Pad47)") (class "Default")
      (node (ref "U11") (pin "47") (pinfunction "PB9_47") (pintype "bidirectional"))
    )
    (net (code "164") (name "unconnected-(U11-PB10-Pad22)") (class "Default")
      (node (ref "U11") (pin "22") (pinfunction "PB10_22") (pintype "bidirectional"))
    )
    (net (code "165") (name "unconnected-(U11-PB11-Pad24)") (class "Default")
      (node (ref "U11") (pin "24") (pinfunction "PB11_24") (pintype "bidirectional"))
    )
    (net (code "166") (name "unconnected-(U11-PB14-Pad27)") (class "Default")
      (node (ref "U11") (pin "27") (pinfunction "PB14_27") (pintype "bidirectional"))
    )
    (net (code "167") (name "unconnected-(U11-PB15-Pad28)") (class "Default")
      (node (ref "U11") (pin "28") (pinfunction "PB15_28") (pintype "bidirectional"))
    )
    (net (code "168") (name "unconnected-(U11-PC4-Pad16)") (class "Default")
      (node (ref "U11") (pin "16") (pinfunction "PC4_16") (pintype "bidirectional"))
    )
    (net (code "169") (name "unconnected-(U11-PC6-Pad29)") (class "Default")
      (node (ref "U11") (pin "29") (pinfunction "PC6_29") (pintype "bidirectional"))
    )
    (net (code "170") (name "unconnected-(U11-PC10-Pad39)") (class "Default")
      (node (ref "U11") (pin "39") (pinfunction "PC10_39") (pintype "bidirectional"))
    )
    (net (code "171") (name "unconnected-(U11-PC11-Pad40)") (class "Default")
      (node (ref "U11") (pin "40") (pinfunction "PC11_40") (pintype "bidirectional"))
    )
    (net (code "172") (name "unconnected-(U11-PC13-Pad2)") (class "Default")
      (node (ref "U11") (pin "2") (pinfunction "PC13_2") (pintype "bidirectional"))
    )
  )
)
